# MKR_IMU_GPS_C_loop_v1_2.net
KiCad netlist of a schematic drawn in EAGLE
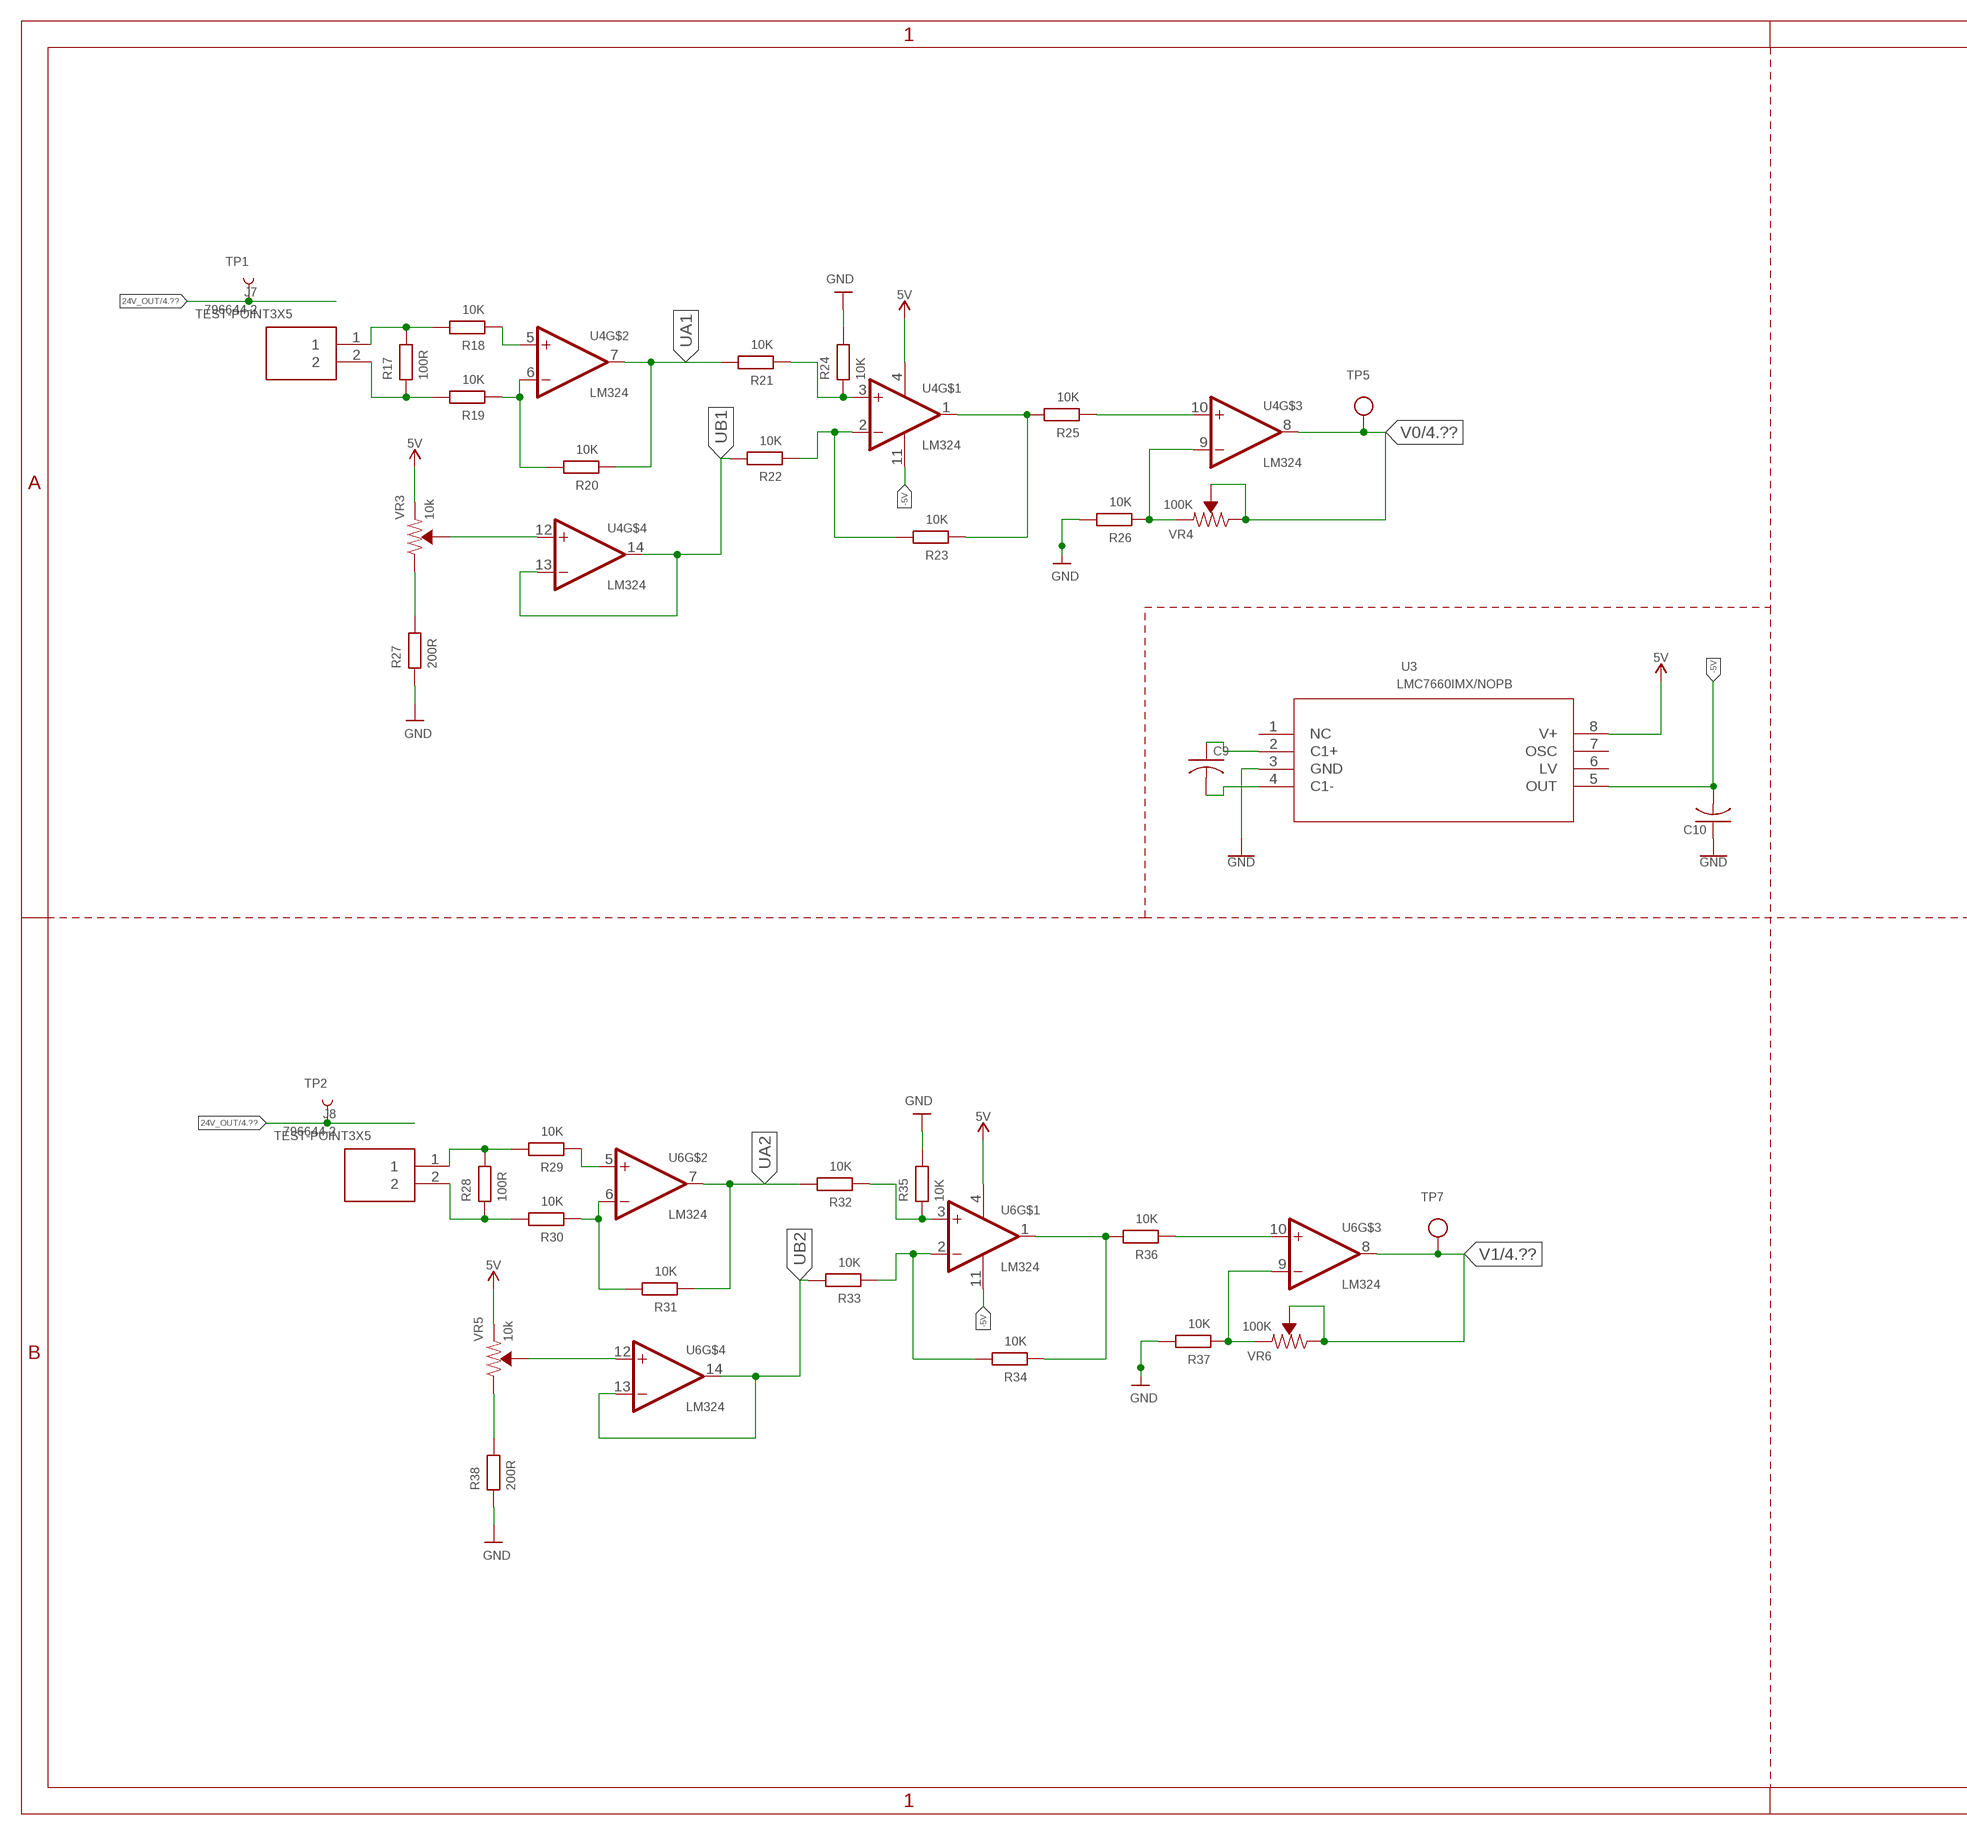
[diagram p0: schematic, sheet 1, part 1 of 2]
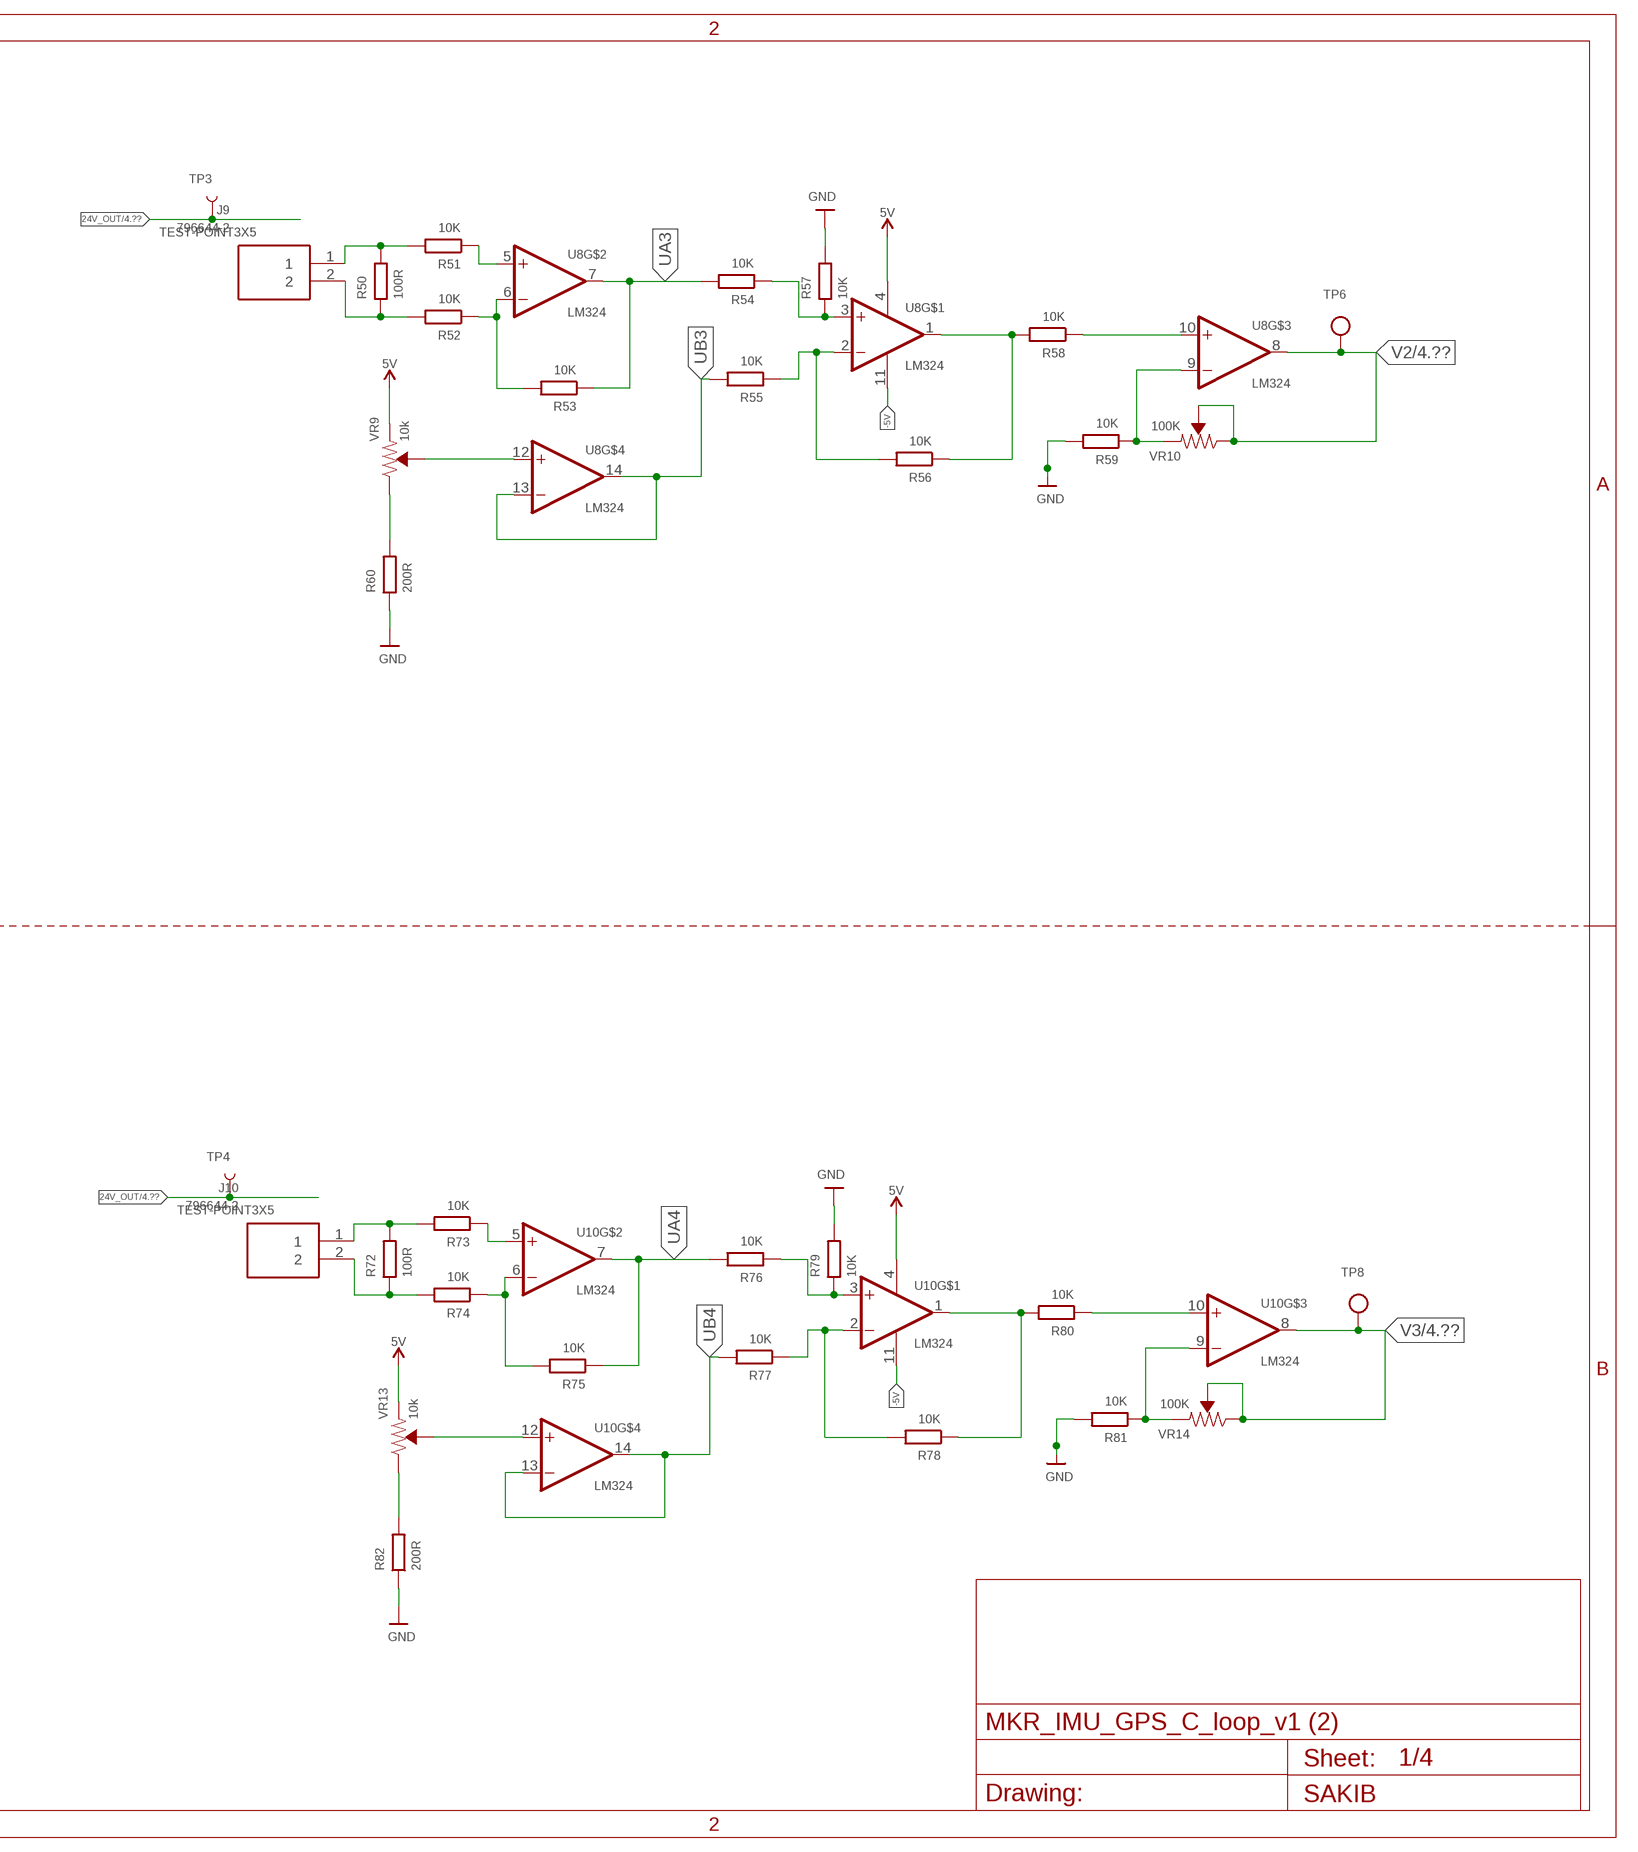
[diagram p1: schematic, sheet 1, part 2 of 2]
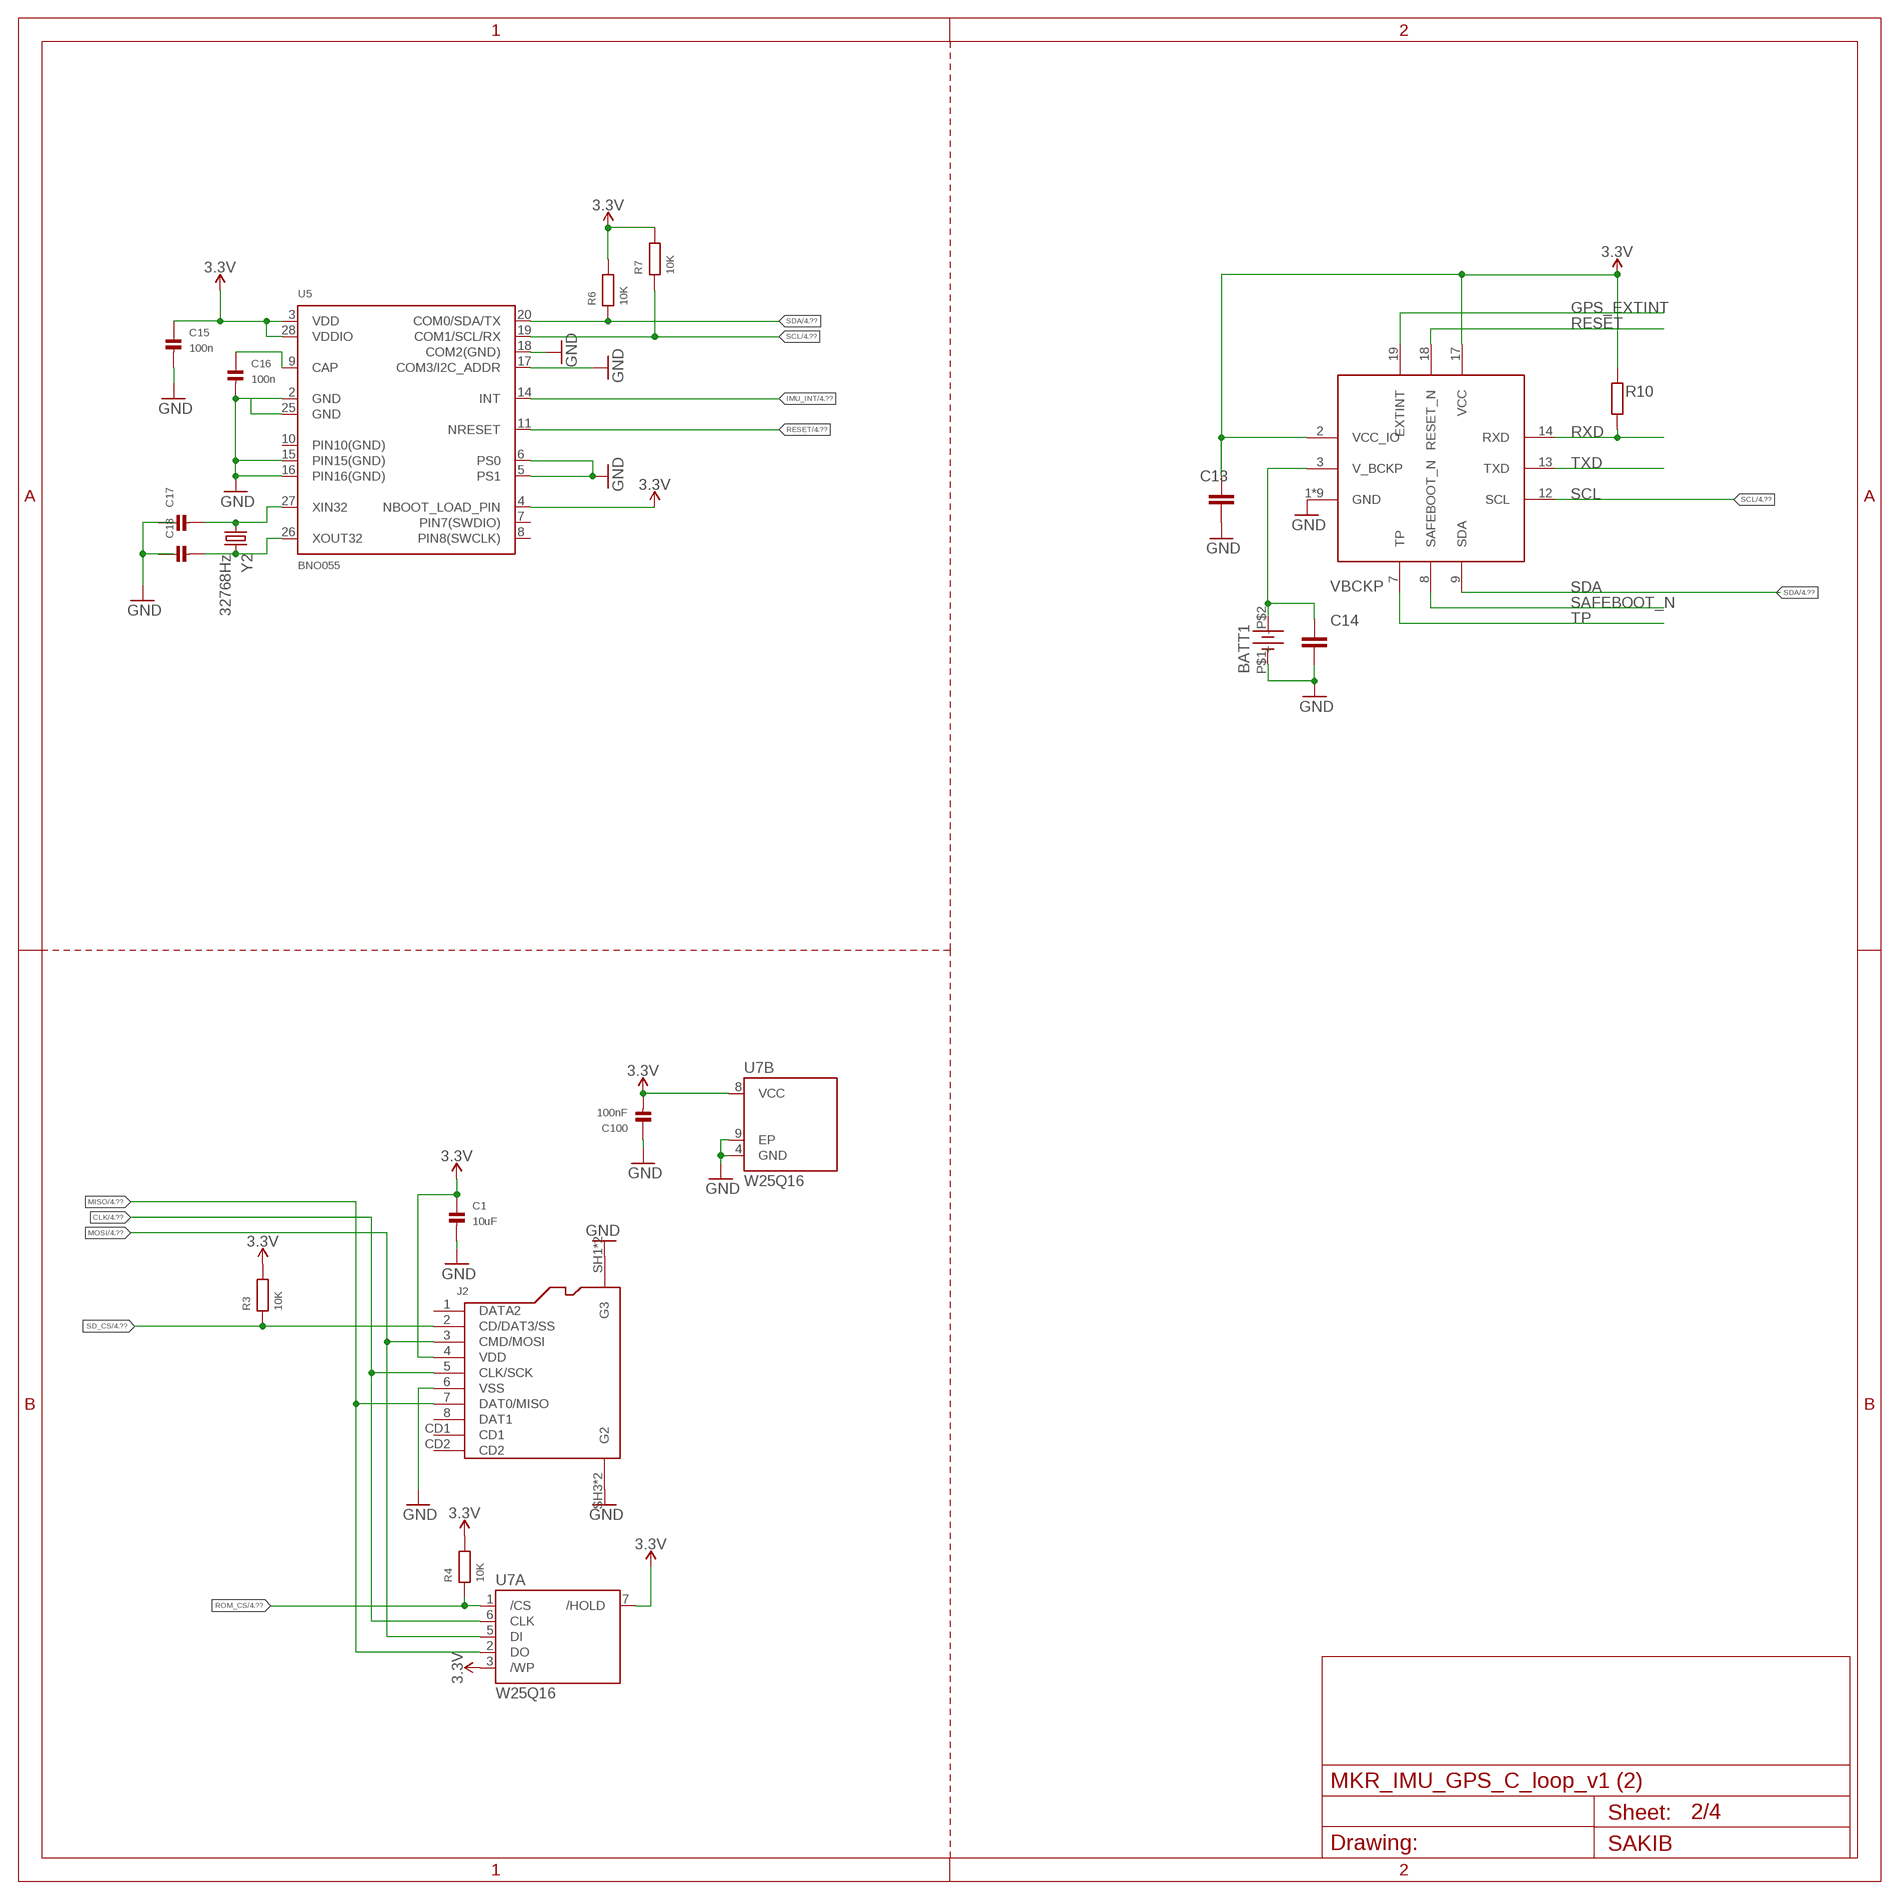
[diagram p2: schematic, sheet 2]
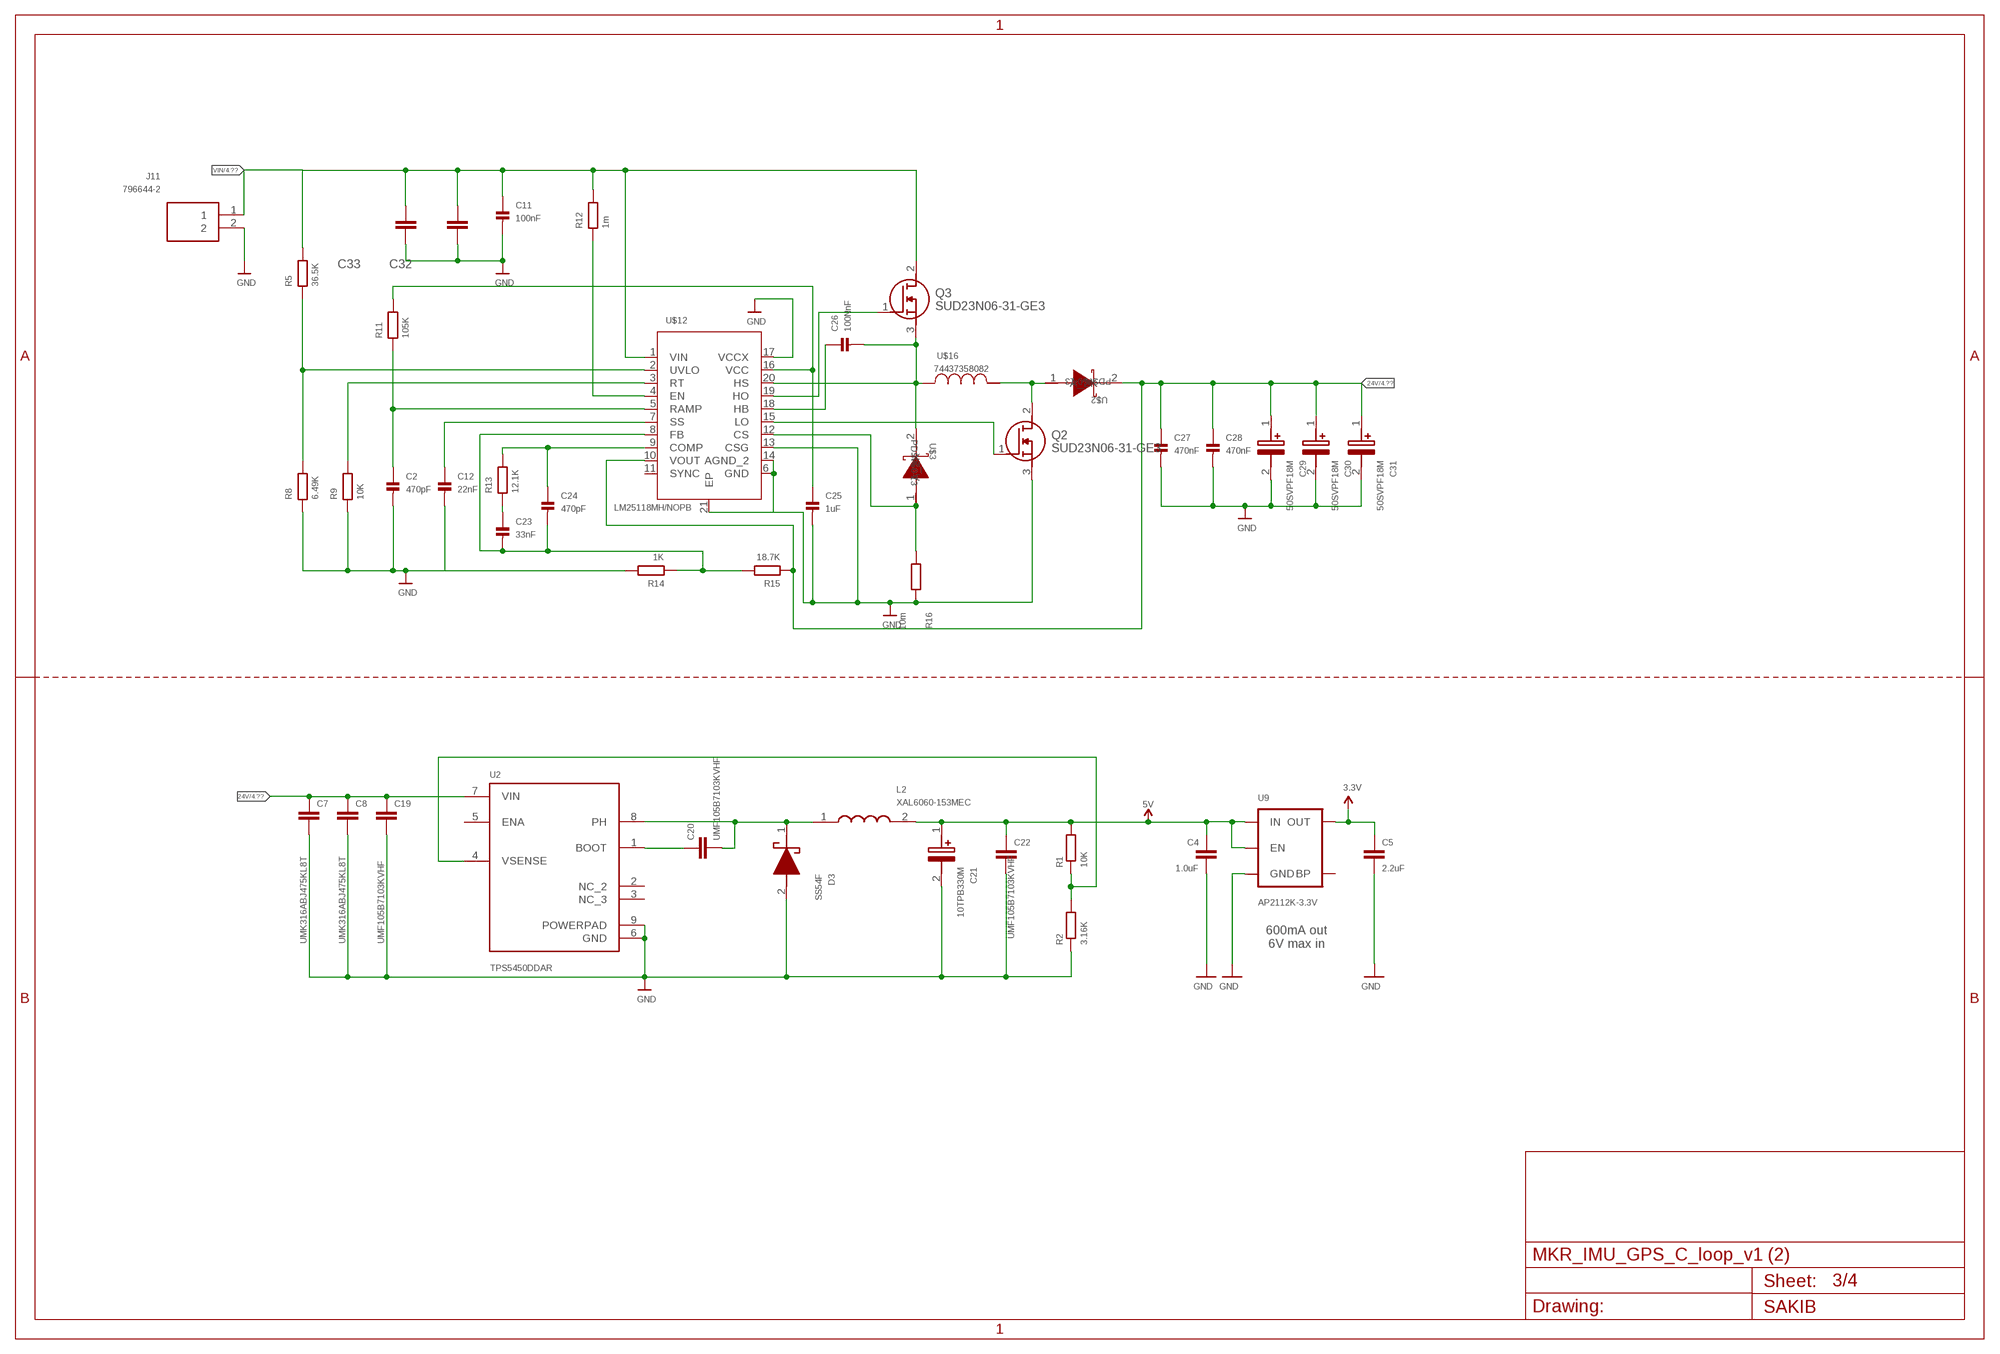
[diagram p3: schematic, sheet 3]
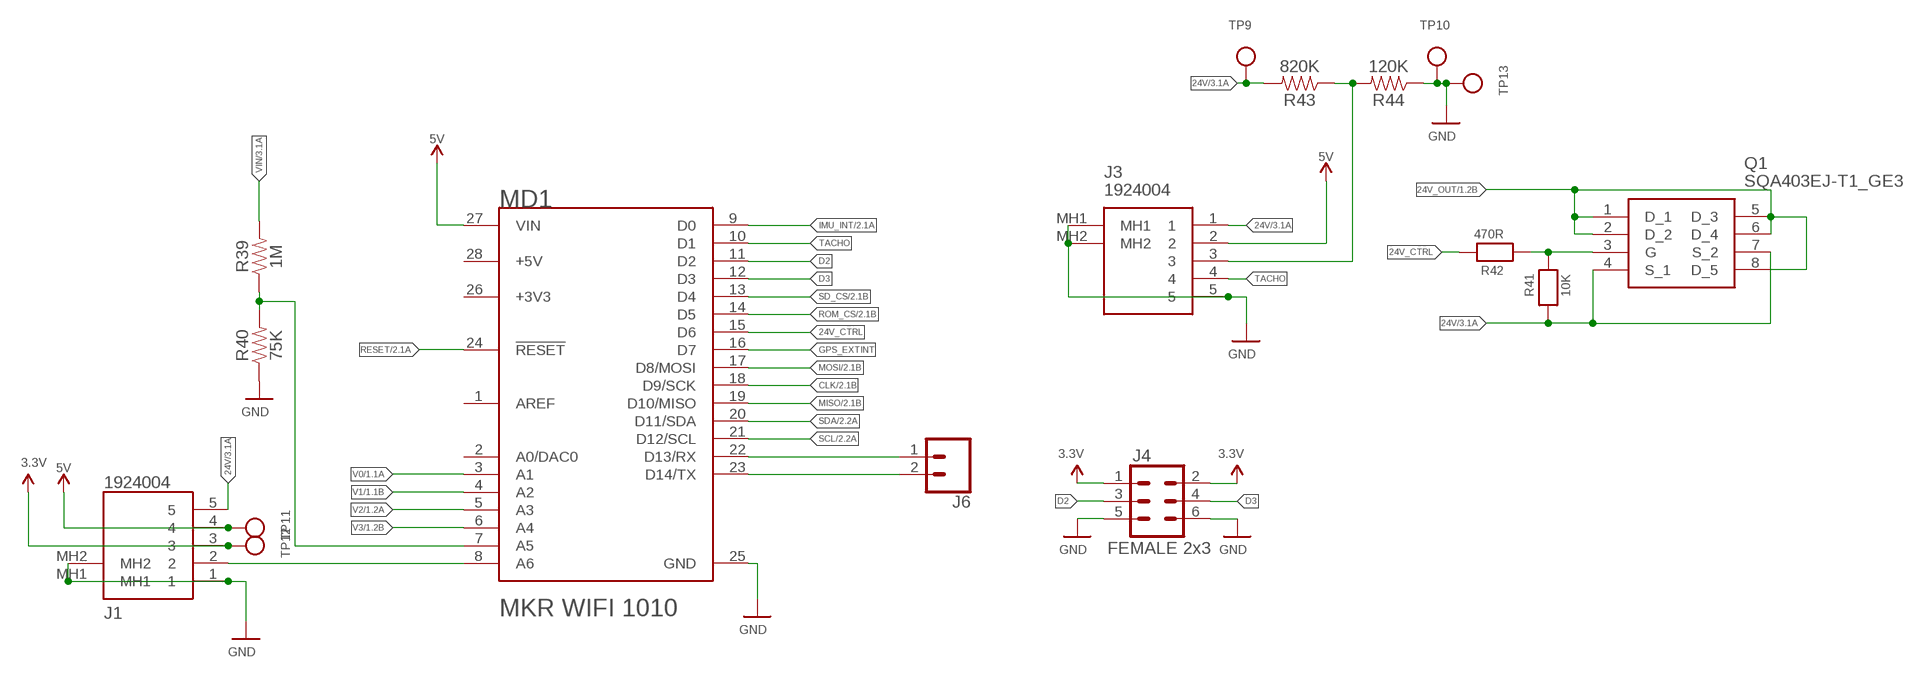
[diagram p4: schematic, sheet 4]

(export (version "E")
  (design (tool "Eeschema 10.0.6"))
  (components
    (comp (ref "C9")
      (value "10uF")
      (footprint "eagle-import:C0402")
      (libsource (lib "eagle-import") (part "C-USC0402"))
    )
    (comp (ref "C10")
      (value "10uF")
      (footprint "eagle-import:C0402")
      (libsource (lib "eagle-import") (part "C-USC0402"))
    )
    (comp (ref "J7")
      (value "796644-2")
      (footprint "eagle-import:7966442")
      (fields (field (name "MOUSER_PART_NUMBER") "571-796644-2"))
      (libsource (lib "eagle-import") (part "796644-2"))
    )
    (comp (ref "J8")
      (value "796644-2")
      (footprint "eagle-import:7966442")
      (fields (field (name "MOUSER_PART_NUMBER") "571-796644-2"))
      (libsource (lib "eagle-import") (part "796644-2"))
    )
    (comp (ref "J9")
      (value "796644-2")
      (footprint "eagle-import:7966442")
      (fields (field (name "MOUSER_PART_NUMBER") "571-796644-2"))
      (libsource (lib "eagle-import") (part "796644-2"))
    )
    (comp (ref "J10")
      (value "796644-2")
      (footprint "eagle-import:7966442")
      (fields (field (name "MOUSER_PART_NUMBER") "571-796644-2"))
      (libsource (lib "eagle-import") (part "796644-2"))
    )
    (comp (ref "R17")
      (value "100R")
      (footprint "eagle-import:R0402")
      (libsource (lib "eagle-import") (part "R-EU_R0402"))
    )
    (comp (ref "R18")
      (value "10K")
      (footprint "eagle-import:R0402")
      (libsource (lib "eagle-import") (part "R-EU_R0402"))
    )
    (comp (ref "R19")
      (value "10K")
      (footprint "eagle-import:R0402")
      (libsource (lib "eagle-import") (part "R-EU_R0402"))
    )
    (comp (ref "R20")
      (value "10K")
      (footprint "eagle-import:R0402")
      (libsource (lib "eagle-import") (part "R-EU_R0402"))
    )
    (comp (ref "R21")
      (value "10K")
      (footprint "eagle-import:R0402")
      (libsource (lib "eagle-import") (part "R-EU_R0402"))
    )
    (comp (ref "R22")
      (value "10K")
      (footprint "eagle-import:R0402")
      (libsource (lib "eagle-import") (part "R-EU_R0402"))
    )
    (comp (ref "R23")
      (value "10K")
      (footprint "eagle-import:R0402")
      (libsource (lib "eagle-import") (part "R-EU_R0402"))
    )
    (comp (ref "R24")
      (value "10K")
      (footprint "eagle-import:R0402")
      (libsource (lib "eagle-import") (part "R-EU_R0402"))
    )
    (comp (ref "R25")
      (value "10K")
      (footprint "eagle-import:R0402")
      (libsource (lib "eagle-import") (part "R-EU_R0402"))
    )
    (comp (ref "R26")
      (value "10K")
      (footprint "eagle-import:R0402")
      (libsource (lib "eagle-import") (part "R-EU_R0402"))
    )
    (comp (ref "R27")
      (value "200R")
      (footprint "eagle-import:R0402")
      (libsource (lib "eagle-import") (part "R-EU_R0402"))
    )
    (comp (ref "R28")
      (value "100R")
      (footprint "eagle-import:R0402")
      (libsource (lib "eagle-import") (part "R-EU_R0402"))
    )
    (comp (ref "R29")
      (value "10K")
      (footprint "eagle-import:R0402")
      (libsource (lib "eagle-import") (part "R-EU_R0402"))
    )
    (comp (ref "R30")
      (value "10K")
      (footprint "eagle-import:R0402")
      (libsource (lib "eagle-import") (part "R-EU_R0402"))
    )
    (comp (ref "R31")
      (value "10K")
      (footprint "eagle-import:R0402")
      (libsource (lib "eagle-import") (part "R-EU_R0402"))
    )
    (comp (ref "R32")
      (value "10K")
      (footprint "eagle-import:R0402")
      (libsource (lib "eagle-import") (part "R-EU_R0402"))
    )
    (comp (ref "R33")
      (value "10K")
      (footprint "eagle-import:R0402")
      (libsource (lib "eagle-import") (part "R-EU_R0402"))
    )
    (comp (ref "R34")
      (value "10K")
      (footprint "eagle-import:R0402")
      (libsource (lib "eagle-import") (part "R-EU_R0402"))
    )
    (comp (ref "R35")
      (value "10K")
      (footprint "eagle-import:R0402")
      (libsource (lib "eagle-import") (part "R-EU_R0402"))
    )
    (comp (ref "R36")
      (value "10K")
      (footprint "eagle-import:R0402")
      (libsource (lib "eagle-import") (part "R-EU_R0402"))
    )
    (comp (ref "R37")
      (value "10K")
      (footprint "eagle-import:R0402")
      (libsource (lib "eagle-import") (part "R-EU_R0402"))
    )
    (comp (ref "R38")
      (value "200R")
      (footprint "eagle-import:R0402")
      (libsource (lib "eagle-import") (part "R-EU_R0402"))
    )
    (comp (ref "R50")
      (value "100R")
      (footprint "eagle-import:R0402")
      (libsource (lib "eagle-import") (part "R-EU_R0402"))
    )
    (comp (ref "R51")
      (value "10K")
      (footprint "eagle-import:R0402")
      (libsource (lib "eagle-import") (part "R-EU_R0402"))
    )
    (comp (ref "R52")
      (value "10K")
      (footprint "eagle-import:R0402")
      (libsource (lib "eagle-import") (part "R-EU_R0402"))
    )
    (comp (ref "R53")
      (value "10K")
      (footprint "eagle-import:R0402")
      (libsource (lib "eagle-import") (part "R-EU_R0402"))
    )
    (comp (ref "R54")
      (value "10K")
      (footprint "eagle-import:R0402")
      (libsource (lib "eagle-import") (part "R-EU_R0402"))
    )
    (comp (ref "R55")
      (value "10K")
      (footprint "eagle-import:R0402")
      (libsource (lib "eagle-import") (part "R-EU_R0402"))
    )
    (comp (ref "R56")
      (value "10K")
      (footprint "eagle-import:R0402")
      (libsource (lib "eagle-import") (part "R-EU_R0402"))
    )
    (comp (ref "R57")
      (value "10K")
      (footprint "eagle-import:R0402")
      (libsource (lib "eagle-import") (part "R-EU_R0402"))
    )
    (comp (ref "R58")
      (value "10K")
      (footprint "eagle-import:R0402")
      (libsource (lib "eagle-import") (part "R-EU_R0402"))
    )
    (comp (ref "R59")
      (value "10K")
      (footprint "eagle-import:R0402")
      (libsource (lib "eagle-import") (part "R-EU_R0402"))
    )
    (comp (ref "R60")
      (value "200R")
      (footprint "eagle-import:R0402")
      (libsource (lib "eagle-import") (part "R-EU_R0402"))
    )
    (comp (ref "R72")
      (value "100R")
      (footprint "eagle-import:R0402")
      (libsource (lib "eagle-import") (part "R-EU_R0402"))
    )
    (comp (ref "R73")
      (value "10K")
      (footprint "eagle-import:R0402")
      (libsource (lib "eagle-import") (part "R-EU_R0402"))
    )
    (comp (ref "R74")
      (value "10K")
      (footprint "eagle-import:R0402")
      (libsource (lib "eagle-import") (part "R-EU_R0402"))
    )
    (comp (ref "R75")
      (value "10K")
      (footprint "eagle-import:R0402")
      (libsource (lib "eagle-import") (part "R-EU_R0402"))
    )
    (comp (ref "R76")
      (value "10K")
      (footprint "eagle-import:R0402")
      (libsource (lib "eagle-import") (part "R-EU_R0402"))
    )
    (comp (ref "R77")
      (value "10K")
      (footprint "eagle-import:R0402")
      (libsource (lib "eagle-import") (part "R-EU_R0402"))
    )
    (comp (ref "R78")
      (value "10K")
      (footprint "eagle-import:R0402")
      (libsource (lib "eagle-import") (part "R-EU_R0402"))
    )
    (comp (ref "R79")
      (value "10K")
      (footprint "eagle-import:R0402")
      (libsource (lib "eagle-import") (part "R-EU_R0402"))
    )
    (comp (ref "R80")
      (value "10K")
      (footprint "eagle-import:R0402")
      (libsource (lib "eagle-import") (part "R-EU_R0402"))
    )
    (comp (ref "R81")
      (value "10K")
      (footprint "eagle-import:R0402")
      (libsource (lib "eagle-import") (part "R-EU_R0402"))
    )
    (comp (ref "R82")
      (value "200R")
      (footprint "eagle-import:R0402")
      (libsource (lib "eagle-import") (part "R-EU_R0402"))
    )
    (comp (ref "TP1")
      (value "TEST-POINT3X5")
      (footprint "eagle-import:PAD.03X.05")
      (libsource (lib "eagle-import") (part "TEST-POINT3X5"))
    )
    (comp (ref "TP2")
      (value "TEST-POINT3X5")
      (footprint "eagle-import:PAD.03X.05")
      (libsource (lib "eagle-import") (part "TEST-POINT3X5"))
    )
    (comp (ref "TP3")
      (value "TEST-POINT3X5")
      (footprint "eagle-import:PAD.03X.05")
      (libsource (lib "eagle-import") (part "TEST-POINT3X5"))
    )
    (comp (ref "TP4")
      (value "TEST-POINT3X5")
      (footprint "eagle-import:PAD.03X.05")
      (libsource (lib "eagle-import") (part "TEST-POINT3X5"))
    )
    (comp (ref "TP5")
      (value "TESTPOINTROUND2MM")
      (footprint "eagle-import:TESTPOINT_ROUND_2MM")
      (libsource (lib "eagle-import") (part "TESTPOINTROUND2MM"))
    )
    (comp (ref "TP6")
      (value "TESTPOINTROUND2MM")
      (footprint "eagle-import:TESTPOINT_ROUND_2MM")
      (libsource (lib "eagle-import") (part "TESTPOINTROUND2MM"))
    )
    (comp (ref "TP7")
      (value "TESTPOINTROUND2MM")
      (footprint "eagle-import:TESTPOINT_ROUND_2MM")
      (libsource (lib "eagle-import") (part "TESTPOINTROUND2MM"))
    )
    (comp (ref "TP8")
      (value "TESTPOINTROUND2MM")
      (footprint "eagle-import:TESTPOINT_ROUND_2MM")
      (libsource (lib "eagle-import") (part "TESTPOINTROUND2MM"))
    )
    (comp (ref "U3")
      (value "LMC7660IMX/NOPB")
      (footprint "eagle-import:M08A_TEX")
      (fields (field (name "COPYRIGHT") "Copyright (C) 2022 Ultra Librarian. All rights reserved."))
      (libsource (lib "eagle-import") (part "LMC7660IMX/NOPB"))
    )
    (comp (ref "U4")
      (value "LM324")
      (footprint "eagle-import:SOIC127P600X175-14N")
      (fields (field (name "MF") "Texas Instruments"))
      (libsource (lib "eagle-import") (part "LM324"))
    )
    (comp (ref "U6")
      (value "LM324")
      (footprint "eagle-import:SOIC127P600X175-14N")
      (fields (field (name "MF") "Texas Instruments"))
      (libsource (lib "eagle-import") (part "LM324"))
    )
    (comp (ref "U8")
      (value "LM324")
      (footprint "eagle-import:SOIC127P600X175-14N")
      (fields (field (name "MF") "Texas Instruments"))
      (libsource (lib "eagle-import") (part "LM324"))
    )
    (comp (ref "U10")
      (value "LM324")
      (footprint "eagle-import:SOIC127P600X175-14N")
      (fields (field (name "MF") "Texas Instruments"))
      (libsource (lib "eagle-import") (part "LM324"))
    )
    (comp (ref "VR3")
      (value "10k")
      (footprint "eagle-import:TRIMPOT-SMD-3MM-CLOSED")
      (libsource (lib "eagle-import") (part "TRIMPOT-SMD-3MM-CLOSED-1/8W-20%"))
    )
    (comp (ref "VR4")
      (value "100K")
      (footprint "eagle-import:TRIMPOT-SMD-3MM-CLOSED")
      (libsource (lib "eagle-import") (part "TRIMPOT-SMD-3MM-CLOSED-1/8W-20%"))
    )
    (comp (ref "VR5")
      (value "10k")
      (footprint "eagle-import:TRIMPOT-SMD-3MM-CLOSED")
      (libsource (lib "eagle-import") (part "TRIMPOT-SMD-3MM-CLOSED-1/8W-20%"))
    )
    (comp (ref "VR6")
      (value "100K")
      (footprint "eagle-import:TRIMPOT-SMD-3MM-CLOSED")
      (libsource (lib "eagle-import") (part "TRIMPOT-SMD-3MM-CLOSED-1/8W-20%"))
    )
    (comp (ref "VR9")
      (value "10k")
      (footprint "eagle-import:TRIMPOT-SMD-3MM-CLOSED")
      (libsource (lib "eagle-import") (part "TRIMPOT-SMD-3MM-CLOSED-1/8W-20%"))
    )
    (comp (ref "VR10")
      (value "100K")
      (footprint "eagle-import:TRIMPOT-SMD-3MM-CLOSED")
      (libsource (lib "eagle-import") (part "TRIMPOT-SMD-3MM-CLOSED-1/8W-20%"))
    )
    (comp (ref "VR13")
      (value "10k")
      (footprint "eagle-import:TRIMPOT-SMD-3MM-CLOSED")
      (libsource (lib "eagle-import") (part "TRIMPOT-SMD-3MM-CLOSED-1/8W-20%"))
    )
    (comp (ref "VR14")
      (value "100K")
      (footprint "eagle-import:TRIMPOT-SMD-3MM-CLOSED")
      (libsource (lib "eagle-import") (part "TRIMPOT-SMD-3MM-CLOSED-1/8W-20%"))
    )
    (comp (ref "J1")
      (value "1924004")
      (footprint "eagle-import:1924004")
      (fields (field (name "MOUSER_PART_NUMBER") "651-1924004"))
      (libsource (lib "eagle-import") (part "1924004"))
    )
    (comp (ref "J3")
      (value "1924004")
      (footprint "eagle-import:1924004")
      (fields (field (name "MOUSER_PART_NUMBER") "651-1924004"))
      (libsource (lib "eagle-import") (part "1924004"))
    )
    (comp (ref "J4")
      (value "FEMALE 2x3")
      (footprint "eagle-import:2X3")
      (libsource (lib "eagle-import") (part "CONN_03X2FEMALE"))
    )
    (comp (ref "J6")
      (value "CONN_02")
      (footprint "eagle-import:1X02")
      (libsource (lib "eagle-import") (part "CONN_02"))
    )
    (comp (ref "MD1")
      (value "ARDUINO_MKR_WIFI_1010ARDUINO_MKR_WIFI_1010_0_0")
      (footprint "eagle-import:ARDUINO_MKR_WIFI_1010_0")
      (fields
        (field (name "DIGIKEY_PART_NUMBER") "1050-1162-ND")
        (field (name "MF") "Arduino")
        (field (name "MOUSER_PART_NUMBER") "782-ABX00023")
      )
      (libsource (lib "eagle-import") (part "ARDUINO_MKR_WIFI_1010ARDUINO_MKR_WIFI_1010_0_0"))
    )
    (comp (ref "Q1")
      (value "SQA403EJ-T1_GE3")
      (footprint "eagle-import:SQA403EJT1_GE3")
      (fields (field (name "MOUSER_PART_NUMBER") "78-SQA403EJ-T1_GE3"))
      (libsource (lib "eagle-import") (part "SQA403EJ-T1_GE3"))
    )
    (comp (ref "R39")
      (value "1M")
      (footprint "eagle-import:0402-TIGHT")
      (libsource (lib "eagle-import") (part "1MOHM-0402T-1/16W-5%"))
    )
    (comp (ref "R40")
      (value "75K")
      (footprint "eagle-import:0402-TIGHT")
      (libsource (lib "eagle-import") (part "1MOHM-0402T-1/16W-5%"))
    )
    (comp (ref "R41")
      (value "10K")
      (footprint "eagle-import:_0402MP")
      (libsource (lib "eagle-import") (part "RESISTOR_0402MP"))
    )
    (comp (ref "R42")
      (value "470R")
      (footprint "eagle-import:_0402MP")
      (libsource (lib "eagle-import") (part "RESISTOR_0402MP"))
    )
    (comp (ref "R43")
      (value "820K")
      (footprint "eagle-import:0402-TIGHT")
      (libsource (lib "eagle-import") (part "1MOHM-0402T-1/16W-5%"))
    )
    (comp (ref "R44")
      (value "120K")
      (footprint "eagle-import:0402-TIGHT")
      (libsource (lib "eagle-import") (part "1MOHM-0402T-1/16W-5%"))
    )
    (comp (ref "TP9")
      (value "TESTPOINTROUND2MM")
      (footprint "eagle-import:TESTPOINT_ROUND_2MM")
      (libsource (lib "eagle-import") (part "TESTPOINTROUND2MM"))
    )
    (comp (ref "TP10")
      (value "TESTPOINTROUND2MM")
      (footprint "eagle-import:TESTPOINT_ROUND_2MM")
      (libsource (lib "eagle-import") (part "TESTPOINTROUND2MM"))
    )
    (comp (ref "TP11")
      (value "TESTPOINTROUND2MM")
      (footprint "eagle-import:TESTPOINT_ROUND_2MM")
      (libsource (lib "eagle-import") (part "TESTPOINTROUND2MM"))
    )
    (comp (ref "TP12")
      (value "TESTPOINTROUND2MM")
      (footprint "eagle-import:TESTPOINT_ROUND_2MM")
      (libsource (lib "eagle-import") (part "TESTPOINTROUND2MM"))
    )
    (comp (ref "TP13")
      (value "TESTPOINTROUND2MM")
      (footprint "eagle-import:TESTPOINT_ROUND_2MM")
      (libsource (lib "eagle-import") (part "TESTPOINTROUND2MM"))
    )
    (comp (ref "C2")
      (value "470pF")
      (footprint "eagle-import:_0402MP")
      (libsource (lib "eagle-import") (part "CAP_CERAMIC_0402MP"))
    )
    (comp (ref "C4")
      (value "1.0uF")
      (footprint "eagle-import:0805")
      (libsource (lib "eagle-import") (part "1.0UF-0805-25V-(+80/-20%)"))
    )
    (comp (ref "C5")
      (value "2.2uF")
      (footprint "eagle-import:0603")
      (libsource (lib "eagle-import") (part "2.2UF-0603-10V-20%"))
    )
    (comp (ref "C7")
      (value "UMK316ABJ475KL8T")
      (footprint "eagle-import:C1206")
      (libsource (lib "eagle-import") (part "C-EUC1206"))
    )
    (comp (ref "C8")
      (value "UMK316ABJ475KL8T")
      (footprint "eagle-import:C1206")
      (libsource (lib "eagle-import") (part "C-EUC1206"))
    )
    (comp (ref "C11")
      (value "100nF")
      (footprint "eagle-import:_0402MP")
      (libsource (lib "eagle-import") (part "CAP_CERAMIC_0402MP"))
    )
    (comp (ref "C12")
      (value "22nF")
      (footprint "eagle-import:_0402MP")
      (libsource (lib "eagle-import") (part "CAP_CERAMIC_0402MP"))
    )
    (comp (ref "C19")
      (value "UMF105B7103KVHF")
      (footprint "eagle-import:C0402")
      (libsource (lib "eagle-import") (part "C-EUC0402"))
    )
    (comp (ref "C20")
      (value "UMF105B7103KVHF")
      (footprint "eagle-import:C0402")
      (libsource (lib "eagle-import") (part "C-EUC0402"))
    )
    (comp (ref "C21")
      (value "10TPB330M")
      (footprint "eagle-import:CAPPM7343X400N")
      (fields (field (name "MOUSER_PART_NUMBER") "667-10TPB330M"))
      (libsource (lib "eagle-import") (part "10TPB330M"))
    )
    (comp (ref "C22")
      (value "UMF105B7103KVHF")
      (footprint "eagle-import:C0402")
      (libsource (lib "eagle-import") (part "C-EUC0402"))
    )
    (comp (ref "C23")
      (value "33nF")
      (footprint "eagle-import:_0402MP")
      (libsource (lib "eagle-import") (part "CAP_CERAMIC_0402MP"))
    )
    (comp (ref "C24")
      (value "470pF")
      (footprint "eagle-import:_0402MP")
      (libsource (lib "eagle-import") (part "CAP_CERAMIC_0402MP"))
    )
    (comp (ref "C25")
      (value "1uF")
      (footprint "eagle-import:_0402MP")
      (libsource (lib "eagle-import") (part "CAP_CERAMIC_0402MP"))
    )
    (comp (ref "C26")
      (value "100NnF")
      (footprint "eagle-import:_0402MP")
      (libsource (lib "eagle-import") (part "CAP_CERAMIC_0402MP"))
    )
    (comp (ref "C27")
      (value "470nF")
      (footprint "eagle-import:_0402MP")
      (libsource (lib "eagle-import") (part "CAP_CERAMIC_0402MP"))
    )
    (comp (ref "C28")
      (value "470nF")
      (footprint "eagle-import:_0402MP")
      (libsource (lib "eagle-import") (part "CAP_CERAMIC_0402MP"))
    )
    (comp (ref "C29")
      (value "50SVPF18M")
      (footprint "eagle-import:16SVF270M")
      (fields (field (name "MOUSER_PART_NUMBER") "667-50SVPF18M"))
      (libsource (lib "eagle-import") (part "50SVPF18M"))
    )
    (comp (ref "C30")
      (value "50SVPF18M")
      (footprint "eagle-import:16SVF270M")
      (fields (field (name "MOUSER_PART_NUMBER") "667-50SVPF18M"))
      (libsource (lib "eagle-import") (part "50SVPF18M"))
    )
    (comp (ref "C31")
      (value "50SVPF18M")
      (footprint "eagle-import:16SVF270M")
      (fields (field (name "MOUSER_PART_NUMBER") "667-50SVPF18M"))
      (libsource (lib "eagle-import") (part "50SVPF18M"))
    )
    (comp (ref "C32")
      (value "C-EUC0402")
      (footprint "eagle-import:C0402")
      (libsource (lib "eagle-import") (part "C-EUC0402"))
    )
    (comp (ref "C33")
      (value "C-EUC0402")
      (footprint "eagle-import:C0402")
      (libsource (lib "eagle-import") (part "C-EUC0402"))
    )
    (comp (ref "D3")
      (value "SS54F")
      (footprint "eagle-import:SODFL4626X130N")
      (libsource (lib "eagle-import") (part "SS54F"))
    )
    (comp (ref "J11")
      (value "796644-2")
      (footprint "eagle-import:7966442")
      (fields (field (name "MOUSER_PART_NUMBER") "571-796644-2"))
      (libsource (lib "eagle-import") (part "796644-2"))
    )
    (comp (ref "L2")
      (value "XAL6060-153MEC")
      (footprint "eagle-import:XAL6060153MEC")
      (fields (field (name "MOUSER_PART_NUMBER") "994-XAL6060-153MEC"))
      (libsource (lib "eagle-import") (part "XAL6060-153MEC"))
    )
    (comp (ref "Q2")
      (value "SUD23N06-31-GE3")
      (footprint "eagle-import:SUD23N0631GE3")
      (fields (field (name "MOUSER_PART_NUMBER") "781-SUD23N06-31-GE3"))
      (libsource (lib "eagle-import") (part "SUD23N06-31-GE3"))
    )
    (comp (ref "Q3")
      (value "SUD23N06-31-GE3")
      (footprint "eagle-import:SUD23N0631GE3")
      (fields (field (name "MOUSER_PART_NUMBER") "781-SUD23N06-31-GE3"))
      (libsource (lib "eagle-import") (part "SUD23N06-31-GE3"))
    )
    (comp (ref "R1")
      (value "10K")
      (footprint "eagle-import:R0402")
      (libsource (lib "eagle-import") (part "R-EU_R0402"))
    )
    (comp (ref "R2")
      (value "3.16K")
      (footprint "eagle-import:R0402")
      (libsource (lib "eagle-import") (part "R-EU_R0402"))
    )
    (comp (ref "R5")
      (value "36.5K")
      (footprint "eagle-import:R0402")
      (libsource (lib "eagle-import") (part "R-EU_R0402"))
    )
    (comp (ref "R8")
      (value "6.49K")
      (footprint "eagle-import:R0402")
      (libsource (lib "eagle-import") (part "R-EU_R0402"))
    )
    (comp (ref "R9")
      (value "10K")
      (footprint "eagle-import:R0402")
      (libsource (lib "eagle-import") (part "R-EU_R0402"))
    )
    (comp (ref "R11")
      (value "105K")
      (footprint "eagle-import:R0402")
      (libsource (lib "eagle-import") (part "R-EU_R0402"))
    )
    (comp (ref "R12")
      (value "1m")
      (footprint "eagle-import:R0402")
      (libsource (lib "eagle-import") (part "R-EU_R0402"))
    )
    (comp (ref "R13")
      (value "12.1K")
      (footprint "eagle-import:R0402")
      (libsource (lib "eagle-import") (part "R-EU_R0402"))
    )
    (comp (ref "R14")
      (value "1K")
      (footprint "eagle-import:R0402")
      (libsource (lib "eagle-import") (part "R-EU_R0402"))
    )
    (comp (ref "R15")
      (value "18.7K")
      (footprint "eagle-import:R0402")
      (libsource (lib "eagle-import") (part "R-EU_R0402"))
    )
    (comp (ref "R16")
      (value "10m")
      (footprint "eagle-import:R0402")
      (libsource (lib "eagle-import") (part "R-EU_R0402"))
    )
    (comp (ref "U$2")
      (value "PDS760-13")
      (footprint "eagle-import:POWERDI5")
      (fields (field (name "MANUFACTURER_PART_NUMBER") "PDS76013"))
      (libsource (lib "eagle-import") (part "PDS760-13"))
    )
    (comp (ref "U$3")
      (value "PDS760-13")
      (footprint "eagle-import:POWERDI5")
      (fields (field (name "MANUFACTURER_PART_NUMBER") "PDS76013"))
      (libsource (lib "eagle-import") (part "PDS760-13"))
    )
    (comp (ref "U$12")
      (value "LM25118MH/NOPB")
      (footprint "eagle-import:MXA20A")
      (fields (field (name "MANUFACTURER_PART_NUMBER") "LM25118MHNOPB"))
      (libsource (lib "eagle-import") (part "LM25118MH/NOPB"))
    )
    (comp (ref "U$16")
      (value "74437358082")
      (footprint "eagle-import:WE-LHMI_8040")
      (libsource (lib "eagle-import") (part "74437358082"))
    )
    (comp (ref "U2")
      (value "TPS5450DDAR")
      (footprint "eagle-import:CONV_TPS5450DDAR")
      (fields (field (name "MF") "Texas Instruments"))
      (libsource (lib "eagle-import") (part "TPS5450DDAR"))
    )
    (comp (ref "U9")
      (value "AP2112K-3.3V")
      (footprint "eagle-import:SOT23-5")
      (libsource (lib "eagle-import") (part "V_REG_LDOSMD"))
    )
    (comp (ref "BATT1")
      (value "BATT-HOLDER_12MM")
      (footprint "eagle-import:BATT-HOLDER_12MM")
      (fields (field (name "MANUFACTURER") "Keystone"))
      (libsource (lib "eagle-import") (part "BATT-HOLDER_12MM"))
    )
    (comp (ref "C1")
      (value "10uF")
      (footprint "eagle-import:_0603MP")
      (libsource (lib "eagle-import") (part "CAP_CERAMIC_0603MP"))
    )
    (comp (ref "C13")
      (value "100n")
      (footprint "eagle-import:C0402")
      (libsource (lib "eagle-import") (part "C-EUC0402"))
    )
    (comp (ref "C14")
      (value "100n")
      (footprint "eagle-import:C0402")
      (fields (field (name "VOLTAGE") "25V"))
      (libsource (lib "eagle-import") (part "C-EUC0402"))
    )
    (comp (ref "C15")
      (value "100n")
      (footprint "eagle-import:_0402MP")
      (libsource (lib "eagle-import") (part "CAP_CERAMIC_0402MP"))
    )
    (comp (ref "C16")
      (value "100n")
      (footprint "eagle-import:_0402MP")
      (libsource (lib "eagle-import") (part "CAP_CERAMIC_0402MP"))
    )
    (comp (ref "C17")
      (value "CAP_CERAMIC_0402MP")
      (footprint "eagle-import:_0402MP")
      (libsource (lib "eagle-import") (part "CAP_CERAMIC_0402MP"))
    )
    (comp (ref "C18")
      (value "CAP_CERAMIC_0402MP")
      (footprint "eagle-import:_0402MP")
      (libsource (lib "eagle-import") (part "CAP_CERAMIC_0402MP"))
    )
    (comp (ref "C100")
      (value "100nF")
      (footprint "eagle-import:_0402MP")
      (libsource (lib "eagle-import") (part "CAP_CERAMIC_0402MP"))
    )
    (comp (ref "IC2")
      (value "SAM-M8Q")
      (footprint "eagle-import:UBLOXLIB_SAM-M8Q")
      (fields (field (name "MANUFACTURER") "U-Blox"))
      (libsource (lib "eagle-import") (part "SAM-M8Q"))
    )
    (comp (ref "J2")
      (value "-")
      (footprint "eagle-import:AMPHENOL_114-00841-68")
      (fields (field (name "MANUFACTURER") "Amphenol"))
      (libsource (lib "eagle-import") (part "SD_AMPHENOL"))
    )
    (comp (ref "R3")
      (value "10K")
      (footprint "eagle-import:R0402")
      (libsource (lib "eagle-import") (part "R-EU_R0402"))
    )
    (comp (ref "R4")
      (value "10K")
      (footprint "eagle-import:R0402")
      (libsource (lib "eagle-import") (part "R-EU_R0402"))
    )
    (comp (ref "R6")
      (value "10K")
      (footprint "eagle-import:R0402")
      (libsource (lib "eagle-import") (part "R-EU_R0402"))
    )
    (comp (ref "R7")
      (value "10K")
      (footprint "eagle-import:R0402")
      (libsource (lib "eagle-import") (part "R-EU_R0402"))
    )
    (comp (ref "R10")
      (value "100k")
      (footprint "eagle-import:R0402")
      (fields (field (name "MPN") "RC0402FR-07100KL"))
      (libsource (lib "eagle-import") (part "R-EU_R0402"))
    )
    (comp (ref "U5")
      (value "BNO055")
      (footprint "eagle-import:BNO055")
      (fields (field (name "MANUFACTURER") "Bosch Sensortec"))
      (libsource (lib "eagle-import") (part "BNO055"))
    )
    (comp (ref "U7")
      (value "W25Q16")
      (footprint "eagle-import:SON9P127_500X600X80L60X41T340X400N")
      (fields (field (name "MANUFACTURER") "Winbond"))
      (libsource (lib "eagle-import") (part "W25QZP16DV?IG"))
    )
    (comp (ref "Y2")
      (value "32768Hz")
      (footprint "eagle-import:ABS07")
      (fields (field (name "MANUFACTURER") "Abracon LLC"))
      (libsource (lib "eagle-import") (part "32.768KHZ"))
    )
  )
  (nets
    (net (code "1") (name "+3V3") (class "Default")
      (node (ref "MD1") (pin "26") (pinfunction "+3V3_26") (pintype "power_in"))
    )
    (net (code "2") (name "+5V") (class "Default")
      (node (ref "MD1") (pin "28") (pinfunction "+5V_28") (pintype "power_in"))
    )
    (net (code "3") (name "-5V") (class "Default")
      (node (ref "C10") (pin "2") (pinfunction "2_2") (pintype "passive"))
      (node (ref "U10") (pin "11") (pinfunction "VCC-_11") (pintype "power_in"))
      (node (ref "U3") (pin "5") (pinfunction "OUT_5") (pintype "power_in"))
      (node (ref "U4") (pin "11") (pinfunction "VCC-_11") (pintype "power_in"))
      (node (ref "U6") (pin "11") (pinfunction "VCC-_11") (pintype "power_in"))
      (node (ref "U8") (pin "11") (pinfunction "VCC-_11") (pintype "power_in"))
    )
    (net (code "4") (name "3.3V") (class "Default")
      (node (ref "C1") (pin "1") (pinfunction "P$1_1") (pintype "passive"))
      (node (ref "C100") (pin "2") (pinfunction "P$2_2") (pintype "passive"))
      (node (ref "C13") (pin "1") (pinfunction "1_1") (pintype "passive"))
      (node (ref "C15") (pin "1") (pinfunction "P$1_1") (pintype "passive"))
      (node (ref "C5") (pin "1") (pinfunction "1_1") (pintype "passive"))
      (node (ref "IC2") (pin "17") (pinfunction "VCC_17") (pintype "bidirectional"))
      (node (ref "IC2") (pin "2") (pinfunction "VCC_IO_2") (pintype "bidirectional"))
      (node (ref "J1") (pin "3") (pinfunction "3_3") (pintype "bidirectional"))
      (node (ref "J2") (pin "4") (pinfunction "VDD_4") (pintype "power_in"))
      (node (ref "J4") (pin "1") (pinfunction "1_1") (pintype "bidirectional"))
      (node (ref "J4") (pin "2") (pinfunction "2_2") (pintype "bidirectional"))
      (node (ref "R10") (pin "2") (pinfunction "2_2") (pintype "passive"))
      (node (ref "R3") (pin "2") (pinfunction "2_2") (pintype "passive"))
      (node (ref "R4") (pin "2") (pinfunction "2_2") (pintype "passive"))
      (node (ref "R6") (pin "2") (pinfunction "2_2") (pintype "passive"))
      (node (ref "R7") (pin "2") (pinfunction "2_2") (pintype "passive"))
      (node (ref "TP12") (pin "P$1") (pinfunction "P$1_P$1") (pintype "bidirectional"))
      (node (ref "U5") (pin "28") (pinfunction "VDDIO_28") (pintype "power_in"))
      (node (ref "U5") (pin "3") (pinfunction "VDD_3") (pintype "power_in"))
      (node (ref "U5") (pin "4") (pinfunction "NBOOT_LOAD_PIN_4") (pintype "bidirectional"))
      (node (ref "U7") (pin "3") (pinfunction "/WP_3") (pintype "input"))
      (node (ref "U7") (pin "7") (pinfunction "/HOLD_7") (pintype "input"))
      (node (ref "U7") (pin "8") (pinfunction "VCC_8") (pintype "power_in"))
      (node (ref "U9") (pin "5") (pinfunction "OUT_5") (pintype "passive"))
    )
    (net (code "5") (name "5V") (class "Default")
      (node (ref "C21") (pin "1") (pinfunction "+_1") (pintype "bidirectional"))
      (node (ref "C22") (pin "1") (pinfunction "1_1") (pintype "passive"))
      (node (ref "C4") (pin "1") (pinfunction "1_1") (pintype "passive"))
      (node (ref "J1") (pin "4") (pinfunction "4_4") (pintype "bidirectional"))
      (node (ref "J3") (pin "2") (pinfunction "2_2") (pintype "bidirectional"))
      (node (ref "L2") (pin "2") (pinfunction "2_2") (pintype "bidirectional"))
      (node (ref "MD1") (pin "27") (pinfunction "VIN_27") (pintype "power_in"))
      (node (ref "R1") (pin "2") (pinfunction "2_2") (pintype "passive"))
      (node (ref "TP11") (pin "P$1") (pinfunction "P$1_P$1") (pintype "bidirectional"))
      (node (ref "U10") (pin "4") (pinfunction "VCC+_4") (pintype "power_in"))
      (node (ref "U3") (pin "8") (pinfunction "V+_8") (pintype "power_in"))
      (node (ref "U4") (pin "4") (pinfunction "VCC+_4") (pintype "power_in"))
      (node (ref "U6") (pin "4") (pinfunction "VCC+_4") (pintype "power_in"))
      (node (ref "U8") (pin "4") (pinfunction "VCC+_4") (pintype "power_in"))
      (node (ref "U9") (pin "1") (pinfunction "IN_1") (pintype "input"))
      (node (ref "U9") (pin "3") (pinfunction "EN_3") (pintype "input"))
      (node (ref "VR13") (pin "1") (pinfunction "CCW_1") (pintype "passive"))
      (node (ref "VR3") (pin "1") (pinfunction "CCW_1") (pintype "passive"))
      (node (ref "VR5") (pin "1") (pinfunction "CCW_1") (pintype "passive"))
      (node (ref "VR9") (pin "1") (pinfunction "CCW_1") (pintype "passive"))
    )
    (net (code "6") (name "24V") (class "Default")
      (node (ref "C19") (pin "1") (pinfunction "1_1") (pintype "passive"))
      (node (ref "C27") (pin "1") (pinfunction "P$1_1") (pintype "passive"))
      (node (ref "C28") (pin "1") (pinfunction "P$1_1") (pintype "passive"))
      (node (ref "C29") (pin "1") (pinfunction "+_1") (pintype "bidirectional"))
      (node (ref "C30") (pin "1") (pinfunction "+_1") (pintype "bidirectional"))
      (node (ref "C31") (pin "1") (pinfunction "+_1") (pintype "bidirectional"))
      (node (ref "C7") (pin "1") (pinfunction "1_1") (pintype "passive"))
      (node (ref "C8") (pin "1") (pinfunction "1_1") (pintype "passive"))
      (node (ref "J1") (pin "5") (pinfunction "5_5") (pintype "bidirectional"))
      (node (ref "J3") (pin "1") (pinfunction "1_1") (pintype "bidirectional"))
      (node (ref "Q1") (pin "4") (pinfunction "S_1_4") (pintype "bidirectional"))
      (node (ref "Q1") (pin "7") (pinfunction "S_2_7") (pintype "bidirectional"))
      (node (ref "R15") (pin "1") (pinfunction "1_1") (pintype "passive"))
      (node (ref "R41") (pin "1") (pinfunction "1_1") (pintype "passive"))
      (node (ref "R43") (pin "2") (pinfunction "2_2") (pintype "passive"))
      (node (ref "TP9") (pin "P$1") (pinfunction "P$1_P$1") (pintype "bidirectional"))
      (node (ref "U$12") (pin "10") (pinfunction "VOUT_10") (pintype "passive"))
      (node (ref "U$2") (pin "2") (pinfunction "K_2") (pintype "passive"))
      (node (ref "U2") (pin "7") (pinfunction "VIN_7") (pintype "power_in"))
    )
    (net (code "7") (name "24V_CTRL") (class "Default")
      (node (ref "MD1") (pin "15") (pinfunction "D6_15") (pintype "bidirectional"))
      (node (ref "R42") (pin "2") (pinfunction "2_2") (pintype "passive"))
    )
    (net (code "8") (name "24V_OUT") (class "Default")
      (node (ref "Q1") (pin "1") (pinfunction "D_1_1") (pintype "bidirectional"))
      (node (ref "Q1") (pin "2") (pinfunction "D_2_2") (pintype "bidirectional"))
      (node (ref "Q1") (pin "5") (pinfunction "D_3_5") (pintype "bidirectional"))
      (node (ref "Q1") (pin "6") (pinfunction "D_4_6") (pintype "bidirectional"))
      (node (ref "Q1") (pin "8") (pinfunction "D_5_8") (pintype "bidirectional"))
      (node (ref "TP1") (pin "1") (pinfunction "1_1") (pintype "bidirectional"))
      (node (ref "TP2") (pin "1") (pinfunction "1_1") (pintype "bidirectional"))
      (node (ref "TP3") (pin "1") (pinfunction "1_1") (pintype "bidirectional"))
      (node (ref "TP4") (pin "1") (pinfunction "1_1") (pintype "bidirectional"))
    )
    (net (code "9") (name "CLK") (class "Default")
      (node (ref "J2") (pin "5") (pinfunction "CLK/SCK_5") (pintype "bidirectional"))
      (node (ref "MD1") (pin "18") (pinfunction "D9/SCK_18") (pintype "bidirectional"))
      (node (ref "U7") (pin "6") (pinfunction "CLK_6") (pintype "input"))
    )
    (net (code "10") (name "D2") (class "Default")
      (node (ref "J4") (pin "3") (pinfunction "3_3") (pintype "bidirectional"))
      (node (ref "MD1") (pin "11") (pinfunction "D2_11") (pintype "bidirectional"))
    )
    (net (code "11") (name "D3") (class "Default")
      (node (ref "J4") (pin "4") (pinfunction "4_4") (pintype "bidirectional"))
      (node (ref "MD1") (pin "12") (pinfunction "D3_12") (pintype "bidirectional"))
    )
    (net (code "12") (name "GND") (class "Default")
      (node (ref "BATT1") (pin "P$1") (pinfunction "-_P$1") (pintype "bidirectional"))
      (node (ref "C1") (pin "2") (pinfunction "P$2_2") (pintype "passive"))
      (node (ref "C10") (pin "1") (pinfunction "1_1") (pintype "passive"))
      (node (ref "C100") (pin "1") (pinfunction "P$1_1") (pintype "passive"))
      (node (ref "C11") (pin "2") (pinfunction "P$2_2") (pintype "passive"))
      (node (ref "C12") (pin "2") (pinfunction "P$2_2") (pintype "passive"))
      (node (ref "C13") (pin "2") (pinfunction "2_2") (pintype "passive"))
      (node (ref "C14") (pin "2") (pinfunction "2_2") (pintype "passive"))
      (node (ref "C15") (pin "2") (pinfunction "P$2_2") (pintype "passive"))
      (node (ref "C16") (pin "2") (pinfunction "P$2_2") (pintype "passive"))
      (node (ref "C17") (pin "1") (pinfunction "P$1_1") (pintype "passive"))
      (node (ref "C18") (pin "1") (pinfunction "P$1_1") (pintype "passive"))
      (node (ref "C19") (pin "2") (pinfunction "2_2") (pintype "passive"))
      (node (ref "C2") (pin "2") (pinfunction "P$2_2") (pintype "passive"))
      (node (ref "C21") (pin "2") (pinfunction "-_2") (pintype "bidirectional"))
      (node (ref "C22") (pin "2") (pinfunction "2_2") (pintype "passive"))
      (node (ref "C25") (pin "2") (pinfunction "P$2_2") (pintype "passive"))
      (node (ref "C27") (pin "2") (pinfunction "P$2_2") (pintype "passive"))
      (node (ref "C28") (pin "2") (pinfunction "P$2_2") (pintype "passive"))
      (node (ref "C29") (pin "2") (pinfunction "-_2") (pintype "bidirectional"))
      (node (ref "C30") (pin "2") (pinfunction "-_2") (pintype "bidirectional"))
      (node (ref "C31") (pin "2") (pinfunction "-_2") (pintype "bidirectional"))
      (node (ref "C32") (pin "1") (pinfunction "1_1") (pintype "passive"))
      (node (ref "C33") (pin "1") (pinfunction "1_1") (pintype "passive"))
      (node (ref "C4") (pin "2") (pinfunction "2_2") (pintype "passive"))
      (node (ref "C5") (pin "2") (pinfunction "2_2") (pintype "passive"))
      (node (ref "C7") (pin "2") (pinfunction "2_2") (pintype "passive"))
      (node (ref "C8") (pin "2") (pinfunction "2_2") (pintype "passive"))
      (node (ref "D3") (pin "2") (pinfunction "A_2") (pintype "bidirectional"))
      (node (ref "IC2") (pin "1") (pinfunction "GND_1") (pintype "bidirectional"))
      (node (ref "IC2") (pin "10") (pinfunction "GND_10") (pintype "bidirectional"))
      (node (ref "IC2") (pin "11") (pinfunction "GND_11") (pintype "bidirectional"))
      (node (ref "IC2") (pin "15") (pinfunction "GND_15") (pintype "bidirectional"))
      (node (ref "IC2") (pin "16") (pinfunction "GND_16") (pintype "bidirectional"))
      (node (ref "IC2") (pin "20") (pinfunction "GND_20") (pintype "bidirectional"))
      (node (ref "IC2") (pin "4") (pinfunction "GND_4") (pintype "bidirectional"))
      (node (ref "IC2") (pin "5") (pinfunction "GND_5") (pintype "bidirectional"))
      (node (ref "IC2") (pin "6") (pinfunction "GND_6") (pintype "bidirectional"))
      (node (ref "J1") (pin "1") (pinfunction "1_1") (pintype "bidirectional"))
      (node (ref "J1") (pin "MH1") (pinfunction "MH1_MH1") (pintype "bidirectional"))
      (node (ref "J1") (pin "MH2") (pinfunction "MH2_MH2") (pintype "bidirectional"))
      (node (ref "J11") (pin "2") (pinfunction "2_2") (pintype "bidirectional"))
      (node (ref "J2") (pin "6") (pinfunction "VSS_6") (pintype "power_in"))
      (node (ref "J2") (pin "SH1") (pinfunction "G3_SH1") (pintype "bidirectional"))
      (node (ref "J2") (pin "SH2") (pinfunction "G3_SH2") (pintype "bidirectional"))
      (node (ref "J2") (pin "SH3") (pinfunction "G2_SH3") (pintype "bidirectional"))
      (node (ref "J2") (pin "SH4") (pinfunction "G2_SH4") (pintype "bidirectional"))
      (node (ref "J3") (pin "5") (pinfunction "5_5") (pintype "bidirectional"))
      (node (ref "J3") (pin "MH1") (pinfunction "MH1_MH1") (pintype "bidirectional"))
      (node (ref "J3") (pin "MH2") (pinfunction "MH2_MH2") (pintype "bidirectional"))
      (node (ref "J4") (pin "5") (pinfunction "5_5") (pintype "bidirectional"))
      (node (ref "J4") (pin "6") (pinfunction "6_6") (pintype "bidirectional"))
      (node (ref "MD1") (pin "25") (pinfunction "GND_25") (pintype "power_in"))
      (node (ref "Q2") (pin "3") (pinfunction "S_3") (pintype "bidirectional"))
      (node (ref "R14") (pin "2") (pinfunction "2_2") (pintype "passive"))
      (node (ref "R16") (pin "2") (pinfunction "2_2") (pintype "passive"))
      (node (ref "R2") (pin "1") (pinfunction "1_1") (pintype "passive"))
      (node (ref "R24") (pin "2") (pinfunction "2_2") (pintype "passive"))
      (node (ref "R26") (pin "2") (pinfunction "2_2") (pintype "passive"))
      (node (ref "R27") (pin "1") (pinfunction "1_1") (pintype "passive"))
      (node (ref "R35") (pin "2") (pinfunction "2_2") (pintype "passive"))
      (node (ref "R37") (pin "2") (pinfunction "2_2") (pintype "passive"))
      (node (ref "R38") (pin "1") (pinfunction "1_1") (pintype "passive"))
      (node (ref "R40") (pin "1") (pinfunction "1_1") (pintype "passive"))
      (node (ref "R44") (pin "1") (pinfunction "1_1") (pintype "passive"))
      (node (ref "R57") (pin "2") (pinfunction "2_2") (pintype "passive"))
      (node (ref "R59") (pin "2") (pinfunction "2_2") (pintype "passive"))
      (node (ref "R60") (pin "1") (pinfunction "1_1") (pintype "passive"))
      (node (ref "R79") (pin "2") (pinfunction "2_2") (pintype "passive"))
      (node (ref "R8") (pin "1") (pinfunction "1_1") (pintype "passive"))
      (node (ref "R81") (pin "2") (pinfunction "2_2") (pintype "passive"))
      (node (ref "R82") (pin "1") (pinfunction "1_1") (pintype "passive"))
      (node (ref "R9") (pin "1") (pinfunction "1_1") (pintype "passive"))
      (node (ref "TP10") (pin "P$1") (pinfunction "P$1_P$1") (pintype "bidirectional"))
      (node (ref "TP13") (pin "P$1") (pinfunction "P$1_P$1") (pintype "bidirectional"))
      (node (ref "U$12") (pin "13") (pinfunction "CSG_13") (pintype "passive"))
      (node (ref "U$12") (pin "14") (pinfunction "AGND_2_14") (pintype "passive"))
      (node (ref "U$12") (pin "17") (pinfunction "VCCX_17") (pintype "passive"))
      (node (ref "U$12") (pin "21") (pinfunction "EP_21") (pintype "bidirectional"))
      (node (ref "U$12") (pin "6") (pinfunction "GND_6") (pintype "bidirectional"))
      (node (ref "U2") (pin "6") (pinfunction "GND_6") (pintype "power_in"))
      (node (ref "U2") (pin "9") (pinfunction "POWERPAD_9") (pintype "power_in"))
      (node (ref "U3") (pin "3") (pinfunction "GND_3") (pintype "power_in"))
      (node (ref "U5") (pin "15") (pinfunction "PIN15(GND)_15") (pintype "bidirectional"))
      (node (ref "U5") (pin "16") (pinfunction "PIN16(GND)_16") (pintype "bidirectional"))
      (node (ref "U5") (pin "17") (pinfunction "COM3/I2C_ADDR_17") (pintype "bidirectional"))
      (node (ref "U5") (pin "18") (pinfunction "COM2(GND)_18") (pintype "bidirectional"))
      (node (ref "U5") (pin "2") (pinfunction "GND_2") (pintype "power_in"))
      (node (ref "U5") (pin "5") (pinfunction "PS1_5") (pintype "input"))
      (node (ref "U5") (pin "6") (pinfunction "PS0_6") (pintype "input"))
      (node (ref "U7") (pin "4") (pinfunction "GND_4") (pintype "power_in"))
      (node (ref "U7") (pin "9") (pinfunction "EP_9") (pintype "passive"))
      (node (ref "U9") (pin "2") (pinfunction "GND_2") (pintype "input"))
    )
    (net (code "13") (name "GPS_EXTINT") (class "Default")
      (node (ref "IC2") (pin "19") (pinfunction "EXTINT_19") (pintype "bidirectional"))
      (node (ref "MD1") (pin "16") (pinfunction "D7_16") (pintype "bidirectional"))
    )
    (net (code "14") (name "IMU_INT") (class "Default")
      (node (ref "MD1") (pin "9") (pinfunction "D0_9") (pintype "bidirectional"))
      (node (ref "U5") (pin "14") (pinfunction "INT_14") (pintype "output"))
    )
    (net (code "15") (name "MISO") (class "Default")
      (node (ref "J2") (pin "7") (pinfunction "DAT0/MISO_7") (pintype "bidirectional"))
      (node (ref "MD1") (pin "19") (pinfunction "D10/MISO_19") (pintype "bidirectional"))
      (node (ref "U7") (pin "2") (pinfunction "DO_2") (pintype "tri_state"))
    )
    (net (code "16") (name "MOSI") (class "Default")
      (node (ref "J2") (pin "3") (pinfunction "CMD/MOSI_3") (pintype "bidirectional"))
      (node (ref "MD1") (pin "17") (pinfunction "D8/MOSI_17") (pintype "bidirectional"))
      (node (ref "U7") (pin "5") (pinfunction "DI_5") (pintype "input"))
    )
    (net (code "17") (name "Net-(C2-P$1)") (class "Default")
      (node (ref "C2") (pin "1") (pinfunction "P$1_1") (pintype "passive"))
      (node (ref "R11") (pin "1") (pinfunction "1_1") (pintype "passive"))
      (node (ref "U$12") (pin "5") (pinfunction "RAMP_5") (pintype "passive"))
    )
    (net (code "18") (name "Net-(C12-P$1)") (class "Default")
      (node (ref "C12") (pin "1") (pinfunction "P$1_1") (pintype "passive"))
      (node (ref "U$12") (pin "7") (pinfunction "SS_7") (pintype "passive"))
    )
    (net (code "19") (name "Net-(C16-P$1)") (class "Default")
      (node (ref "C16") (pin "1") (pinfunction "P$1_1") (pintype "passive"))
      (node (ref "U5") (pin "9") (pinfunction "CAP_9") (pintype "passive"))
    )
    (net (code "20") (name "Net-(C17-P$2)") (class "Default")
      (node (ref "C17") (pin "2") (pinfunction "P$2_2") (pintype "passive"))
      (node (ref "U5") (pin "27") (pinfunction "XIN32_27") (pintype "input"))
      (node (ref "Y2") (pin "1") (pinfunction "1_1") (pintype "passive"))
    )
    (net (code "21") (name "Net-(C18-P$2)") (class "Default")
      (node (ref "C18") (pin "2") (pinfunction "P$2_2") (pintype "passive"))
      (node (ref "U5") (pin "26") (pinfunction "XOUT32_26") (pintype "output"))
      (node (ref "Y2") (pin "2") (pinfunction "2_2") (pintype "passive"))
    )
    (net (code "22") (name "Net-(C23-P$1)") (class "Default")
      (node (ref "C23") (pin "1") (pinfunction "P$1_1") (pintype "passive"))
      (node (ref "R13") (pin "1") (pinfunction "1_1") (pintype "passive"))
    )
    (net (code "23") (name "Net-(C23-P$2)") (class "Default")
      (node (ref "C23") (pin "2") (pinfunction "P$2_2") (pintype "passive"))
      (node (ref "C24") (pin "2") (pinfunction "P$2_2") (pintype "passive"))
      (node (ref "R14") (pin "1") (pinfunction "1_1") (pintype "passive"))
      (node (ref "R15") (pin "2") (pinfunction "2_2") (pintype "passive"))
      (node (ref "U$12") (pin "8") (pinfunction "FB_8") (pintype "passive"))
    )
    (net (code "24") (name "Net-(C24-P$1)") (class "Default")
      (node (ref "C24") (pin "1") (pinfunction "P$1_1") (pintype "passive"))
      (node (ref "R13") (pin "2") (pinfunction "2_2") (pintype "passive"))
      (node (ref "U$12") (pin "9") (pinfunction "COMP_9") (pintype "passive"))
    )
    (net (code "25") (name "Net-(C25-P$1)") (class "Default")
      (node (ref "C25") (pin "1") (pinfunction "P$1_1") (pintype "passive"))
      (node (ref "R11") (pin "2") (pinfunction "2_2") (pintype "passive"))
      (node (ref "U$12") (pin "16") (pinfunction "VCC_16") (pintype "passive"))
    )
    (net (code "26") (name "Net-(C26-P$1)") (class "Default")
      (node (ref "C26") (pin "1") (pinfunction "P$1_1") (pintype "passive"))
      (node (ref "U$12") (pin "18") (pinfunction "HB_18") (pintype "passive"))
    )
    (net (code "27") (name "Net-(C26-P$2)") (class "Default")
      (node (ref "C26") (pin "2") (pinfunction "P$2_2") (pintype "passive"))
      (node (ref "Q3") (pin "3") (pinfunction "S_3") (pintype "bidirectional"))
      (node (ref "U$12") (pin "20") (pinfunction "HS_20") (pintype "passive"))
      (node (ref "U$16") (pin "2") (pinfunction "2_2") (pintype "passive"))
      (node (ref "U$3") (pin "2") (pinfunction "K_2") (pintype "passive"))
    )
    (net (code "28") (name "Net-(D3-K)") (class "Default")
      (node (ref "C20") (pin "2") (pinfunction "2_2") (pintype "passive"))
      (node (ref "D3") (pin "1") (pinfunction "K_1") (pintype "bidirectional"))
      (node (ref "L2") (pin "1") (pinfunction "1_1") (pintype "bidirectional"))
      (node (ref "U2") (pin "8") (pinfunction "PH_8") (pintype "output"))
    )
    (net (code "29") (name "Net-(J3-Pad3)") (class "Default")
      (node (ref "J3") (pin "3") (pinfunction "3_3") (pintype "bidirectional"))
      (node (ref "R43") (pin "1") (pinfunction "1_1") (pintype "passive"))
      (node (ref "R44") (pin "2") (pinfunction "2_2") (pintype "passive"))
    )
    (net (code "30") (name "Net-(J7-Pad1)") (class "Default")
      (node (ref "J7") (pin "1") (pinfunction "1_1") (pintype "bidirectional"))
      (node (ref "R17") (pin "2") (pinfunction "2_2") (pintype "passive"))
      (node (ref "R18") (pin "2") (pinfunction "2_2") (pintype "passive"))
    )
    (net (code "31") (name "Net-(J7-Pad2)") (class "Default")
      (node (ref "J7") (pin "2") (pinfunction "2_2") (pintype "bidirectional"))
      (node (ref "R17") (pin "1") (pinfunction "1_1") (pintype "passive"))
      (node (ref "R19") (pin "2") (pinfunction "2_2") (pintype "passive"))
    )
    (net (code "32") (name "Net-(J8-Pad1)") (class "Default")
      (node (ref "J8") (pin "1") (pinfunction "1_1") (pintype "bidirectional"))
      (node (ref "R28") (pin "2") (pinfunction "2_2") (pintype "passive"))
      (node (ref "R29") (pin "2") (pinfunction "2_2") (pintype "passive"))
    )
    (net (code "33") (name "Net-(J8-Pad2)") (class "Default")
      (node (ref "J8") (pin "2") (pinfunction "2_2") (pintype "bidirectional"))
      (node (ref "R28") (pin "1") (pinfunction "1_1") (pintype "passive"))
      (node (ref "R30") (pin "2") (pinfunction "2_2") (pintype "passive"))
    )
    (net (code "34") (name "Net-(J9-Pad1)") (class "Default")
      (node (ref "J9") (pin "1") (pinfunction "1_1") (pintype "bidirectional"))
      (node (ref "R50") (pin "2") (pinfunction "2_2") (pintype "passive"))
      (node (ref "R51") (pin "2") (pinfunction "2_2") (pintype "passive"))
    )
    (net (code "35") (name "Net-(J9-Pad2)") (class "Default")
      (node (ref "J9") (pin "2") (pinfunction "2_2") (pintype "bidirectional"))
      (node (ref "R50") (pin "1") (pinfunction "1_1") (pintype "passive"))
      (node (ref "R52") (pin "2") (pinfunction "2_2") (pintype "passive"))
    )
    (net (code "36") (name "Net-(J10-Pad1)") (class "Default")
      (node (ref "J10") (pin "1") (pinfunction "1_1") (pintype "bidirectional"))
      (node (ref "R72") (pin "2") (pinfunction "2_2") (pintype "passive"))
      (node (ref "R73") (pin "2") (pinfunction "2_2") (pintype "passive"))
    )
    (net (code "37") (name "Net-(J10-Pad2)") (class "Default")
      (node (ref "J10") (pin "2") (pinfunction "2_2") (pintype "bidirectional"))
      (node (ref "R72") (pin "1") (pinfunction "1_1") (pintype "passive"))
      (node (ref "R74") (pin "2") (pinfunction "2_2") (pintype "passive"))
    )
    (net (code "38") (name "Net-(MD1-A5)") (class "Default")
      (node (ref "MD1") (pin "7") (pinfunction "A5_7") (pintype "bidirectional"))
      (node (ref "R39") (pin "1") (pinfunction "1_1") (pintype "passive"))
      (node (ref "R40") (pin "2") (pinfunction "2_2") (pintype "passive"))
    )
    (net (code "39") (name "Net-(MD1-A6)") (class "Default")
      (node (ref "J1") (pin "2") (pinfunction "2_2") (pintype "bidirectional"))
      (node (ref "MD1") (pin "8") (pinfunction "A6_8") (pintype "bidirectional"))
    )
    (net (code "40") (name "Net-(MD1-D13{slash}RX)") (class "Default")
      (node (ref "J6") (pin "1") (pinfunction "1_1") (pintype "passive"))
      (node (ref "MD1") (pin "22") (pinfunction "D13/RX_22") (pintype "bidirectional"))
    )
    (net (code "41") (name "Net-(MD1-D14{slash}TX)") (class "Default")
      (node (ref "J6") (pin "2") (pinfunction "2_2") (pintype "passive"))
      (node (ref "MD1") (pin "23") (pinfunction "D14/TX_23") (pintype "bidirectional"))
    )
    (net (code "42") (name "Net-(Q1-G)") (class "Default")
      (node (ref "Q1") (pin "3") (pinfunction "G_3") (pintype "bidirectional"))
      (node (ref "R41") (pin "2") (pinfunction "2_2") (pintype "passive"))
      (node (ref "R42") (pin "1") (pinfunction "1_1") (pintype "passive"))
    )
    (net (code "43") (name "Net-(Q2-D)") (class "Default")
      (node (ref "Q2") (pin "2") (pinfunction "D_2") (pintype "bidirectional"))
      (node (ref "U$16") (pin "1") (pinfunction "1_1") (pintype "passive"))
      (node (ref "U$2") (pin "1") (pinfunction "A_2_1") (pintype "passive"))
    )
    (net (code "44") (name "Net-(Q2-G)") (class "Default")
      (node (ref "Q2") (pin "1") (pinfunction "G_1") (pintype "bidirectional"))
      (node (ref "U$12") (pin "15") (pinfunction "LO_15") (pintype "passive"))
    )
    (net (code "45") (name "Net-(Q3-G)") (class "Default")
      (node (ref "Q3") (pin "1") (pinfunction "G_1") (pintype "bidirectional"))
      (node (ref "U$12") (pin "19") (pinfunction "HO_19") (pintype "passive"))
    )
    (net (code "46") (name "Net-(U$12-CS)") (class "Default")
      (node (ref "R16") (pin "1") (pinfunction "1_1") (pintype "passive"))
      (node (ref "U$12") (pin "12") (pinfunction "CS_12") (pintype "passive"))
      (node (ref "U$3") (pin "1") (pinfunction "A_2_1") (pintype "passive"))
    )
    (net (code "47") (name "Net-(U$12-EN)") (class "Default")
      (node (ref "R12") (pin "1") (pinfunction "1_1") (pintype "passive"))
      (node (ref "U$12") (pin "4") (pinfunction "EN_4") (pintype "passive"))
    )
    (net (code "48") (name "Net-(U$12-RT)") (class "Default")
      (node (ref "R9") (pin "2") (pinfunction "2_2") (pintype "passive"))
      (node (ref "U$12") (pin "3") (pinfunction "RT_3") (pintype "passive"))
    )
    (net (code "49") (name "Net-(U$12-UVLO)") (class "Default")
      (node (ref "R5") (pin "1") (pinfunction "1_1") (pintype "passive"))
      (node (ref "R8") (pin "2") (pinfunction "2_2") (pintype "passive"))
      (node (ref "U$12") (pin "2") (pinfunction "UVLO_2") (pintype "passive"))
    )
    (net (code "50") (name "Net-(U2-BOOT)") (class "Default")
      (node (ref "C20") (pin "1") (pinfunction "1_1") (pintype "passive"))
      (node (ref "U2") (pin "1") (pinfunction "BOOT_1") (pintype "output"))
    )
    (net (code "51") (name "Net-(U2-VSENSE)") (class "Default")
      (node (ref "R1") (pin "1") (pinfunction "1_1") (pintype "passive"))
      (node (ref "R2") (pin "2") (pinfunction "2_2") (pintype "passive"))
      (node (ref "U2") (pin "4") (pinfunction "VSENSE_4") (pintype "input"))
    )
    (net (code "52") (name "Net-(U3-C1+)") (class "Default")
      (node (ref "C9") (pin "1") (pinfunction "1_1") (pintype "passive"))
      (node (ref "U3") (pin "2") (pinfunction "C1+_2") (pintype "input"))
    )
    (net (code "53") (name "Net-(U3-C1-)") (class "Default")
      (node (ref "C9") (pin "2") (pinfunction "2_2") (pintype "passive"))
      (node (ref "U3") (pin "4") (pinfunction "C1-_4") (pintype "input"))
    )
    (net (code "54") (name "Net-(U4A-INVERTING_INPUT1)") (class "Default")
      (node (ref "R22") (pin "1") (pinfunction "1_1") (pintype "passive"))
      (node (ref "R23") (pin "2") (pinfunction "2_2") (pintype "passive"))
      (node (ref "U4") (pin "2") (pinfunction "INVERTING_INPUT1_2") (pintype "input"))
    )
    (net (code "55") (name "Net-(U4A-NON-INVERTING_INPUT1)") (class "Default")
      (node (ref "R21") (pin "1") (pinfunction "1_1") (pintype "passive"))
      (node (ref "R24") (pin "1") (pinfunction "1_1") (pintype "passive"))
      (node (ref "U4") (pin "3") (pinfunction "NON-INVERTING_INPUT1_3") (pintype "input"))
    )
    (net (code "56") (name "Net-(U4A-OUTPUT1)") (class "Default")
      (node (ref "R23") (pin "1") (pinfunction "1_1") (pintype "passive"))
      (node (ref "R25") (pin "2") (pinfunction "2_2") (pintype "passive"))
      (node (ref "U4") (pin "1") (pinfunction "OUTPUT1_1") (pintype "output"))
    )
    (net (code "57") (name "Net-(U4B-INVERTING_INPUT2)") (class "Default")
      (node (ref "R19") (pin "1") (pinfunction "1_1") (pintype "passive"))
      (node (ref "R20") (pin "2") (pinfunction "2_2") (pintype "passive"))
      (node (ref "U4") (pin "6") (pinfunction "INVERTING_INPUT2_6") (pintype "input"))
    )
    (net (code "58") (name "Net-(U4B-NON-INVERTING_INPUT2)") (class "Default")
      (node (ref "R18") (pin "1") (pinfunction "1_1") (pintype "passive"))
      (node (ref "U4") (pin "5") (pinfunction "NON-INVERTING_INPUT2_5") (pintype "input"))
    )
    (net (code "59") (name "Net-(U4C-INVERTING_INPUT3)") (class "Default")
      (node (ref "R26") (pin "1") (pinfunction "1_1") (pintype "passive"))
      (node (ref "U4") (pin "9") (pinfunction "INVERTING_INPUT3_9") (pintype "input"))
      (node (ref "VR4") (pin "1") (pinfunction "CCW_1") (pintype "passive"))
    )
    (net (code "60") (name "Net-(U4C-NON-INVERTING_INPUT3)") (class "Default")
      (node (ref "R25") (pin "1") (pinfunction "1_1") (pintype "passive"))
      (node (ref "U4") (pin "10") (pinfunction "NON-INVERTING_INPUT3_10") (pintype "input"))
    )
    (net (code "61") (name "Net-(U4D-NON-INVERTING_INPUT4)") (class "Default")
      (node (ref "U4") (pin "12") (pinfunction "NON-INVERTING_INPUT4_12") (pintype "input"))
      (node (ref "VR3") (pin "2") (pinfunction "WIPER_2") (pintype "passive"))
    )
    (net (code "62") (name "Net-(U6A-INVERTING_INPUT1)") (class "Default")
      (node (ref "R33") (pin "1") (pinfunction "1_1") (pintype "passive"))
      (node (ref "R34") (pin "2") (pinfunction "2_2") (pintype "passive"))
      (node (ref "U6") (pin "2") (pinfunction "INVERTING_INPUT1_2") (pintype "input"))
    )
    (net (code "63") (name "Net-(U6A-NON-INVERTING_INPUT1)") (class "Default")
      (node (ref "R32") (pin "1") (pinfunction "1_1") (pintype "passive"))
      (node (ref "R35") (pin "1") (pinfunction "1_1") (pintype "passive"))
      (node (ref "U6") (pin "3") (pinfunction "NON-INVERTING_INPUT1_3") (pintype "input"))
    )
    (net (code "64") (name "Net-(U6A-OUTPUT1)") (class "Default")
      (node (ref "R34") (pin "1") (pinfunction "1_1") (pintype "passive"))
      (node (ref "R36") (pin "2") (pinfunction "2_2") (pintype "passive"))
      (node (ref "U6") (pin "1") (pinfunction "OUTPUT1_1") (pintype "output"))
    )
    (net (code "65") (name "Net-(U6B-INVERTING_INPUT2)") (class "Default")
      (node (ref "R30") (pin "1") (pinfunction "1_1") (pintype "passive"))
      (node (ref "R31") (pin "2") (pinfunction "2_2") (pintype "passive"))
      (node (ref "U6") (pin "6") (pinfunction "INVERTING_INPUT2_6") (pintype "input"))
    )
    (net (code "66") (name "Net-(U6B-NON-INVERTING_INPUT2)") (class "Default")
      (node (ref "R29") (pin "1") (pinfunction "1_1") (pintype "passive"))
      (node (ref "U6") (pin "5") (pinfunction "NON-INVERTING_INPUT2_5") (pintype "input"))
    )
    (net (code "67") (name "Net-(U6C-INVERTING_INPUT3)") (class "Default")
      (node (ref "R37") (pin "1") (pinfunction "1_1") (pintype "passive"))
      (node (ref "U6") (pin "9") (pinfunction "INVERTING_INPUT3_9") (pintype "input"))
      (node (ref "VR6") (pin "1") (pinfunction "CCW_1") (pintype "passive"))
    )
    (net (code "68") (name "Net-(U6C-NON-INVERTING_INPUT3)") (class "Default")
      (node (ref "R36") (pin "1") (pinfunction "1_1") (pintype "passive"))
      (node (ref "U6") (pin "10") (pinfunction "NON-INVERTING_INPUT3_10") (pintype "input"))
    )
    (net (code "69") (name "Net-(U6D-NON-INVERTING_INPUT4)") (class "Default")
      (node (ref "U6") (pin "12") (pinfunction "NON-INVERTING_INPUT4_12") (pintype "input"))
      (node (ref "VR5") (pin "2") (pinfunction "WIPER_2") (pintype "passive"))
    )
    (net (code "70") (name "Net-(U8A-INVERTING_INPUT1)") (class "Default")
      (node (ref "R55") (pin "1") (pinfunction "1_1") (pintype "passive"))
      (node (ref "R56") (pin "2") (pinfunction "2_2") (pintype "passive"))
      (node (ref "U8") (pin "2") (pinfunction "INVERTING_INPUT1_2") (pintype "input"))
    )
    (net (code "71") (name "Net-(U8A-NON-INVERTING_INPUT1)") (class "Default")
      (node (ref "R54") (pin "1") (pinfunction "1_1") (pintype "passive"))
      (node (ref "R57") (pin "1") (pinfunction "1_1") (pintype "passive"))
      (node (ref "U8") (pin "3") (pinfunction "NON-INVERTING_INPUT1_3") (pintype "input"))
    )
    (net (code "72") (name "Net-(U8A-OUTPUT1)") (class "Default")
      (node (ref "R56") (pin "1") (pinfunction "1_1") (pintype "passive"))
      (node (ref "R58") (pin "2") (pinfunction "2_2") (pintype "passive"))
      (node (ref "U8") (pin "1") (pinfunction "OUTPUT1_1") (pintype "output"))
    )
    (net (code "73") (name "Net-(U8B-INVERTING_INPUT2)") (class "Default")
      (node (ref "R52") (pin "1") (pinfunction "1_1") (pintype "passive"))
      (node (ref "R53") (pin "2") (pinfunction "2_2") (pintype "passive"))
      (node (ref "U8") (pin "6") (pinfunction "INVERTING_INPUT2_6") (pintype "input"))
    )
    (net (code "74") (name "Net-(U8B-NON-INVERTING_INPUT2)") (class "Default")
      (node (ref "R51") (pin "1") (pinfunction "1_1") (pintype "passive"))
      (node (ref "U8") (pin "5") (pinfunction "NON-INVERTING_INPUT2_5") (pintype "input"))
    )
    (net (code "75") (name "Net-(U8C-INVERTING_INPUT3)") (class "Default")
      (node (ref "R59") (pin "1") (pinfunction "1_1") (pintype "passive"))
      (node (ref "U8") (pin "9") (pinfunction "INVERTING_INPUT3_9") (pintype "input"))
      (node (ref "VR10") (pin "1") (pinfunction "CCW_1") (pintype "passive"))
    )
    (net (code "76") (name "Net-(U8C-NON-INVERTING_INPUT3)") (class "Default")
      (node (ref "R58") (pin "1") (pinfunction "1_1") (pintype "passive"))
      (node (ref "U8") (pin "10") (pinfunction "NON-INVERTING_INPUT3_10") (pintype "input"))
    )
    (net (code "77") (name "Net-(U8D-NON-INVERTING_INPUT4)") (class "Default")
      (node (ref "U8") (pin "12") (pinfunction "NON-INVERTING_INPUT4_12") (pintype "input"))
      (node (ref "VR9") (pin "2") (pinfunction "WIPER_2") (pintype "passive"))
    )
    (net (code "78") (name "Net-(U10A-INVERTING_INPUT1)") (class "Default")
      (node (ref "R77") (pin "1") (pinfunction "1_1") (pintype "passive"))
      (node (ref "R78") (pin "2") (pinfunction "2_2") (pintype "passive"))
      (node (ref "U10") (pin "2") (pinfunction "INVERTING_INPUT1_2") (pintype "input"))
    )
    (net (code "79") (name "Net-(U10A-NON-INVERTING_INPUT1)") (class "Default")
      (node (ref "R76") (pin "1") (pinfunction "1_1") (pintype "passive"))
      (node (ref "R79") (pin "1") (pinfunction "1_1") (pintype "passive"))
      (node (ref "U10") (pin "3") (pinfunction "NON-INVERTING_INPUT1_3") (pintype "input"))
    )
    (net (code "80") (name "Net-(U10A-OUTPUT1)") (class "Default")
      (node (ref "R78") (pin "1") (pinfunction "1_1") (pintype "passive"))
      (node (ref "R80") (pin "2") (pinfunction "2_2") (pintype "passive"))
      (node (ref "U10") (pin "1") (pinfunction "OUTPUT1_1") (pintype "output"))
    )
    (net (code "81") (name "Net-(U10B-INVERTING_INPUT2)") (class "Default")
      (node (ref "R74") (pin "1") (pinfunction "1_1") (pintype "passive"))
      (node (ref "R75") (pin "2") (pinfunction "2_2") (pintype "passive"))
      (node (ref "U10") (pin "6") (pinfunction "INVERTING_INPUT2_6") (pintype "input"))
    )
    (net (code "82") (name "Net-(U10B-NON-INVERTING_INPUT2)") (class "Default")
      (node (ref "R73") (pin "1") (pinfunction "1_1") (pintype "passive"))
      (node (ref "U10") (pin "5") (pinfunction "NON-INVERTING_INPUT2_5") (pintype "input"))
    )
    (net (code "83") (name "Net-(U10C-INVERTING_INPUT3)") (class "Default")
      (node (ref "R81") (pin "1") (pinfunction "1_1") (pintype "passive"))
      (node (ref "U10") (pin "9") (pinfunction "INVERTING_INPUT3_9") (pintype "input"))
      (node (ref "VR14") (pin "1") (pinfunction "CCW_1") (pintype "passive"))
    )
    (net (code "84") (name "Net-(U10C-NON-INVERTING_INPUT3)") (class "Default")
      (node (ref "R80") (pin "1") (pinfunction "1_1") (pintype "passive"))
      (node (ref "U10") (pin "10") (pinfunction "NON-INVERTING_INPUT3_10") (pintype "input"))
    )
    (net (code "85") (name "Net-(U10D-NON-INVERTING_INPUT4)") (class "Default")
      (node (ref "U10") (pin "12") (pinfunction "NON-INVERTING_INPUT4_12") (pintype "input"))
      (node (ref "VR13") (pin "2") (pinfunction "WIPER_2") (pintype "passive"))
    )
    (net (code "86") (name "Net-(VR3-CW)") (class "Default")
      (node (ref "R27") (pin "2") (pinfunction "2_2") (pintype "passive"))
      (node (ref "VR3") (pin "3") (pinfunction "CW_3") (pintype "passive"))
    )
    (net (code "87") (name "Net-(VR5-CW)") (class "Default")
      (node (ref "R38") (pin "2") (pinfunction "2_2") (pintype "passive"))
      (node (ref "VR5") (pin "3") (pinfunction "CW_3") (pintype "passive"))
    )
    (net (code "88") (name "Net-(VR9-CW)") (class "Default")
      (node (ref "R60") (pin "2") (pinfunction "2_2") (pintype "passive"))
      (node (ref "VR9") (pin "3") (pinfunction "CW_3") (pintype "passive"))
    )
    (net (code "89") (name "Net-(VR13-CW)") (class "Default")
      (node (ref "R82") (pin "2") (pinfunction "2_2") (pintype "passive"))
      (node (ref "VR13") (pin "3") (pinfunction "CW_3") (pintype "passive"))
    )
    (net (code "90") (name "RESET") (class "Default")
      (node (ref "IC2") (pin "18") (pinfunction "RESET_N_18") (pintype "bidirectional"))
      (node (ref "MD1") (pin "24") (pinfunction "~{RESET}_24") (pintype "input"))
      (node (ref "U5") (pin "11") (pinfunction "NRESET_11") (pintype "bidirectional"))
    )
    (net (code "91") (name "ROM_CS") (class "Default")
      (node (ref "MD1") (pin "14") (pinfunction "D5_14") (pintype "bidirectional"))
      (node (ref "R4") (pin "1") (pinfunction "1_1") (pintype "passive"))
      (node (ref "U7") (pin "1") (pinfunction "/CS_1") (pintype "input"))
    )
    (net (code "92") (name "RXD") (class "Default")
      (node (ref "IC2") (pin "14") (pinfunction "RXD_14") (pintype "bidirectional"))
      (node (ref "R10") (pin "1") (pinfunction "1_1") (pintype "passive"))
    )
    (net (code "93") (name "SAFEBOOT_N") (class "Default")
      (node (ref "IC2") (pin "8") (pinfunction "SAFEBOOT_N_8") (pintype "bidirectional"))
    )
    (net (code "94") (name "SCL") (class "Default")
      (node (ref "IC2") (pin "12") (pinfunction "SCL_12") (pintype "bidirectional"))
      (node (ref "MD1") (pin "21") (pinfunction "D12/SCL_21") (pintype "bidirectional"))
      (node (ref "R7") (pin "1") (pinfunction "1_1") (pintype "passive"))
      (node (ref "U5") (pin "19") (pinfunction "COM1/SCL/RX_19") (pintype "bidirectional"))
    )
    (net (code "95") (name "SDA") (class "Default")
      (node (ref "IC2") (pin "9") (pinfunction "SDA_9") (pintype "bidirectional"))
      (node (ref "MD1") (pin "20") (pinfunction "D11/SDA_20") (pintype "bidirectional"))
      (node (ref "R6") (pin "1") (pinfunction "1_1") (pintype "passive"))
      (node (ref "U5") (pin "20") (pinfunction "COM0/SDA/TX_20") (pintype "bidirectional"))
    )
    (net (code "96") (name "SD_CS") (class "Default")
      (node (ref "J2") (pin "2") (pinfunction "CD/DAT3/SS_2") (pintype "bidirectional"))
      (node (ref "MD1") (pin "13") (pinfunction "D4_13") (pintype "bidirectional"))
      (node (ref "R3") (pin "1") (pinfunction "1_1") (pintype "passive"))
    )
    (net (code "97") (name "TACHO") (class "Default")
      (node (ref "J3") (pin "4") (pinfunction "4_4") (pintype "bidirectional"))
      (node (ref "MD1") (pin "10") (pinfunction "D1_10") (pintype "bidirectional"))
    )
    (net (code "98") (name "TP") (class "Default")
      (node (ref "IC2") (pin "7") (pinfunction "TP_7") (pintype "bidirectional"))
    )
    (net (code "99") (name "TXD") (class "Default")
      (node (ref "IC2") (pin "13") (pinfunction "TXD_13") (pintype "bidirectional"))
    )
    (net (code "100") (name "UA1") (class "Default")
      (node (ref "R20") (pin "1") (pinfunction "1_1") (pintype "passive"))
      (node (ref "R21") (pin "2") (pinfunction "2_2") (pintype "passive"))
      (node (ref "U4") (pin "7") (pinfunction "OUTPUT2_7") (pintype "output"))
    )
    (net (code "101") (name "UA2") (class "Default")
      (node (ref "R31") (pin "1") (pinfunction "1_1") (pintype "passive"))
      (node (ref "R32") (pin "2") (pinfunction "2_2") (pintype "passive"))
      (node (ref "U6") (pin "7") (pinfunction "OUTPUT2_7") (pintype "output"))
    )
    (net (code "102") (name "UA3") (class "Default")
      (node (ref "R53") (pin "1") (pinfunction "1_1") (pintype "passive"))
      (node (ref "R54") (pin "2") (pinfunction "2_2") (pintype "passive"))
      (node (ref "U8") (pin "7") (pinfunction "OUTPUT2_7") (pintype "output"))
    )
    (net (code "103") (name "UA4") (class "Default")
      (node (ref "R75") (pin "1") (pinfunction "1_1") (pintype "passive"))
      (node (ref "R76") (pin "2") (pinfunction "2_2") (pintype "passive"))
      (node (ref "U10") (pin "7") (pinfunction "OUTPUT2_7") (pintype "output"))
    )
    (net (code "104") (name "UB1") (class "Default")
      (node (ref "R22") (pin "2") (pinfunction "2_2") (pintype "passive"))
      (node (ref "U4") (pin "13") (pinfunction "INVERTING_INPUT4_13") (pintype "input"))
      (node (ref "U4") (pin "14") (pinfunction "OUTPUT4_14") (pintype "output"))
    )
    (net (code "105") (name "UB2") (class "Default")
      (node (ref "R33") (pin "2") (pinfunction "2_2") (pintype "passive"))
      (node (ref "U6") (pin "13") (pinfunction "INVERTING_INPUT4_13") (pintype "input"))
      (node (ref "U6") (pin "14") (pinfunction "OUTPUT4_14") (pintype "output"))
    )
    (net (code "106") (name "UB3") (class "Default")
      (node (ref "R55") (pin "2") (pinfunction "2_2") (pintype "passive"))
      (node (ref "U8") (pin "13") (pinfunction "INVERTING_INPUT4_13") (pintype "input"))
      (node (ref "U8") (pin "14") (pinfunction "OUTPUT4_14") (pintype "output"))
    )
    (net (code "107") (name "UB4") (class "Default")
      (node (ref "R77") (pin "2") (pinfunction "2_2") (pintype "passive"))
      (node (ref "U10") (pin "13") (pinfunction "INVERTING_INPUT4_13") (pintype "input"))
      (node (ref "U10") (pin "14") (pinfunction "OUTPUT4_14") (pintype "output"))
    )
    (net (code "108") (name "V0") (class "Default")
      (node (ref "MD1") (pin "3") (pinfunction "A1_3") (pintype "bidirectional"))
      (node (ref "TP5") (pin "P$1") (pinfunction "P$1_P$1") (pintype "bidirectional"))
      (node (ref "U4") (pin "8") (pinfunction "OUTPUT3_8") (pintype "output"))
      (node (ref "VR4") (pin "2") (pinfunction "WIPER_2") (pintype "passive"))
      (node (ref "VR4") (pin "3") (pinfunction "CW_3") (pintype "passive"))
    )
    (net (code "109") (name "V1") (class "Default")
      (node (ref "MD1") (pin "4") (pinfunction "A2_4") (pintype "bidirectional"))
      (node (ref "TP7") (pin "P$1") (pinfunction "P$1_P$1") (pintype "bidirectional"))
      (node (ref "U6") (pin "8") (pinfunction "OUTPUT3_8") (pintype "output"))
      (node (ref "VR6") (pin "2") (pinfunction "WIPER_2") (pintype "passive"))
      (node (ref "VR6") (pin "3") (pinfunction "CW_3") (pintype "passive"))
    )
    (net (code "110") (name "V2") (class "Default")
      (node (ref "MD1") (pin "5") (pinfunction "A3_5") (pintype "bidirectional"))
      (node (ref "TP6") (pin "P$1") (pinfunction "P$1_P$1") (pintype "bidirectional"))
      (node (ref "U8") (pin "8") (pinfunction "OUTPUT3_8") (pintype "output"))
      (node (ref "VR10") (pin "2") (pinfunction "WIPER_2") (pintype "passive"))
      (node (ref "VR10") (pin "3") (pinfunction "CW_3") (pintype "passive"))
    )
    (net (code "111") (name "V3") (class "Default")
      (node (ref "MD1") (pin "6") (pinfunction "A4_6") (pintype "bidirectional"))
      (node (ref "TP8") (pin "P$1") (pinfunction "P$1_P$1") (pintype "bidirectional"))
      (node (ref "U10") (pin "8") (pinfunction "OUTPUT3_8") (pintype "output"))
      (node (ref "VR14") (pin "2") (pinfunction "WIPER_2") (pintype "passive"))
      (node (ref "VR14") (pin "3") (pinfunction "CW_3") (pintype "passive"))
    )
    (net (code "112") (name "VBCKP") (class "Default")
      (node (ref "BATT1") (pin "P$2") (pinfunction "+_P$2") (pintype "bidirectional"))
      (node (ref "C14") (pin "1") (pinfunction "1_1") (pintype "passive"))
      (node (ref "IC2") (pin "3") (pinfunction "V_BCKP_3") (pintype "bidirectional"))
    )
    (net (code "113") (name "VIN") (class "Default")
      (node (ref "C11") (pin "1") (pinfunction "P$1_1") (pintype "passive"))
      (node (ref "C32") (pin "2") (pinfunction "2_2") (pintype "passive"))
      (node (ref "C33") (pin "2") (pinfunction "2_2") (pintype "passive"))
      (node (ref "J11") (pin "1") (pinfunction "1_1") (pintype "bidirectional"))
      (node (ref "Q3") (pin "2") (pinfunction "D_2") (pintype "bidirectional"))
      (node (ref "R12") (pin "2") (pinfunction "2_2") (pintype "passive"))
      (node (ref "R39") (pin "2") (pinfunction "2_2") (pintype "passive"))
      (node (ref "R5") (pin "2") (pinfunction "2_2") (pintype "passive"))
      (node (ref "U$12") (pin "1") (pinfunction "VIN_1") (pintype "passive"))
    )
    (net (code "114") (name "unconnected-(J2-DAT1-Pad8)") (class "Default")
      (node (ref "J2") (pin "8") (pinfunction "DAT1_8") (pintype "bidirectional"))
    )
    (net (code "115") (name "unconnected-(J2-DATA2-Pad1)") (class "Default")
      (node (ref "J2") (pin "1") (pinfunction "DATA2_1") (pintype "bidirectional"))
    )
    (net (code "116") (name "unconnected-(J2-PadCD1)") (class "Default")
      (node (ref "J2") (pin "CD1") (pinfunction "CD1_CD1") (pintype "bidirectional"))
    )
    (net (code "117") (name "unconnected-(J2-PadCD2)") (class "Default")
      (node (ref "J2") (pin "CD2") (pinfunction "CD2_CD2") (pintype "bidirectional"))
    )
    (net (code "118") (name "unconnected-(MD1-A0{slash}DAC0-Pad2)") (class "Default")
      (node (ref "MD1") (pin "2") (pinfunction "A0/DAC0_2") (pintype "bidirectional"))
    )
    (net (code "119") (name "unconnected-(MD1-AREF-Pad1)") (class "Default")
      (node (ref "MD1") (pin "1") (pinfunction "AREF_1") (pintype "input"))
    )
    (net (code "120") (name "unconnected-(U$12-SYNC-Pad11)") (class "Default")
      (node (ref "U$12") (pin "11") (pinfunction "SYNC_11") (pintype "passive"))
    )
    (net (code "121") (name "unconnected-(U2-ENA-Pad5)") (class "Default")
      (node (ref "U2") (pin "5") (pinfunction "ENA_5") (pintype "input"))
    )
    (net (code "122") (name "unconnected-(U2-NC_2-Pad2)") (class "Default")
      (node (ref "U2") (pin "2") (pinfunction "NC_2_2") (pintype "no_connect"))
    )
    (net (code "123") (name "unconnected-(U2-NC_3-Pad3)") (class "Default")
      (node (ref "U2") (pin "3") (pinfunction "NC_3_3") (pintype "no_connect"))
    )
    (net (code "124") (name "unconnected-(U3-LV-Pad6)") (class "Default")
      (node (ref "U3") (pin "6") (pinfunction "LV_6") (pintype "input"))
    )
    (net (code "125") (name "unconnected-(U3-NC-Pad1)") (class "Default")
      (node (ref "U3") (pin "1") (pinfunction "NC_1") (pintype "passive"))
    )
    (net (code "126") (name "unconnected-(U3-OSC-Pad7)") (class "Default")
      (node (ref "U3") (pin "7") (pinfunction "OSC_7") (pintype "input"))
    )
    (net (code "127") (name "unconnected-(U5-GND-Pad25)") (class "Default")
      (node (ref "U5") (pin "25") (pinfunction "GND_25") (pintype "power_in"))
    )
    (net (code "128") (name "unconnected-(U5-PIN7(SWDIO)-Pad7)") (class "Default")
      (node (ref "U5") (pin "7") (pinfunction "PIN7(SWDIO)_7") (pintype "bidirectional"))
    )
    (net (code "129") (name "unconnected-(U5-PIN8(SWCLK)-Pad8)") (class "Default")
      (node (ref "U5") (pin "8") (pinfunction "PIN8(SWCLK)_8") (pintype "bidirectional"))
    )
    (net (code "130") (name "unconnected-(U5-PIN10(GND)-Pad10)") (class "Default")
      (node (ref "U5") (pin "10") (pinfunction "PIN10(GND)_10") (pintype "bidirectional"))
    )
    (net (code "131") (name "unconnected-(U9-BP-Pad4)") (class "Default")
      (node (ref "U9") (pin "4") (pinfunction "BP_4") (pintype "input"))
    )
  )
)
